# ESP32_WATCH_V1_0.net
KiCad netlist of a schematic drawn in EAGLE
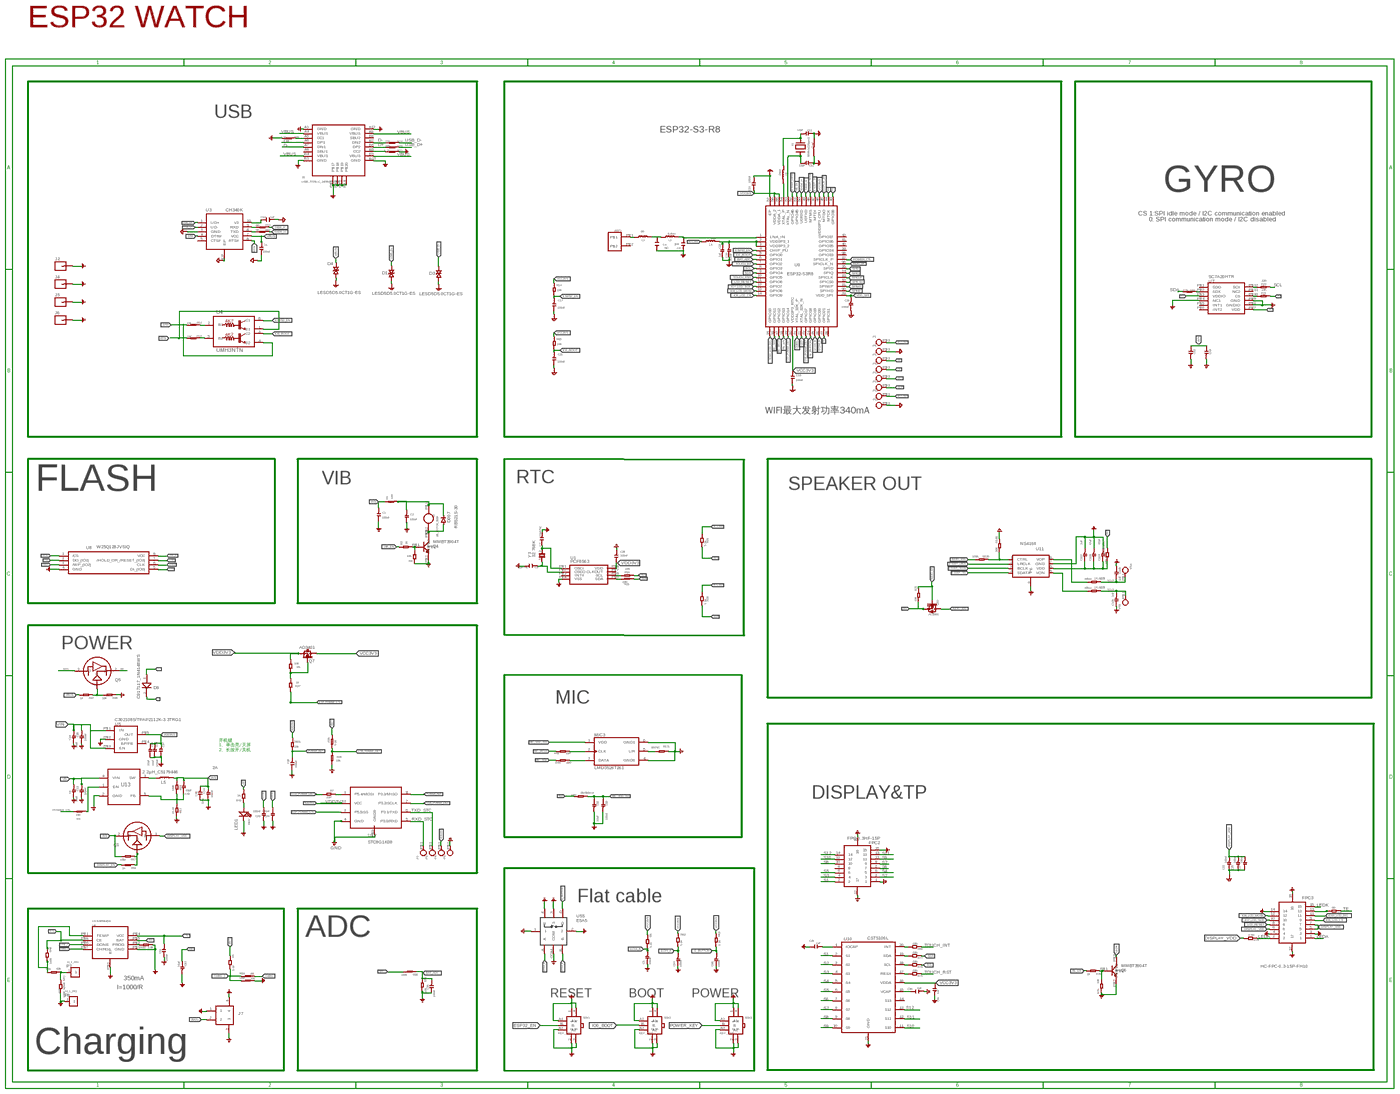
[diagram p0: schematic, sheet 1, overview]
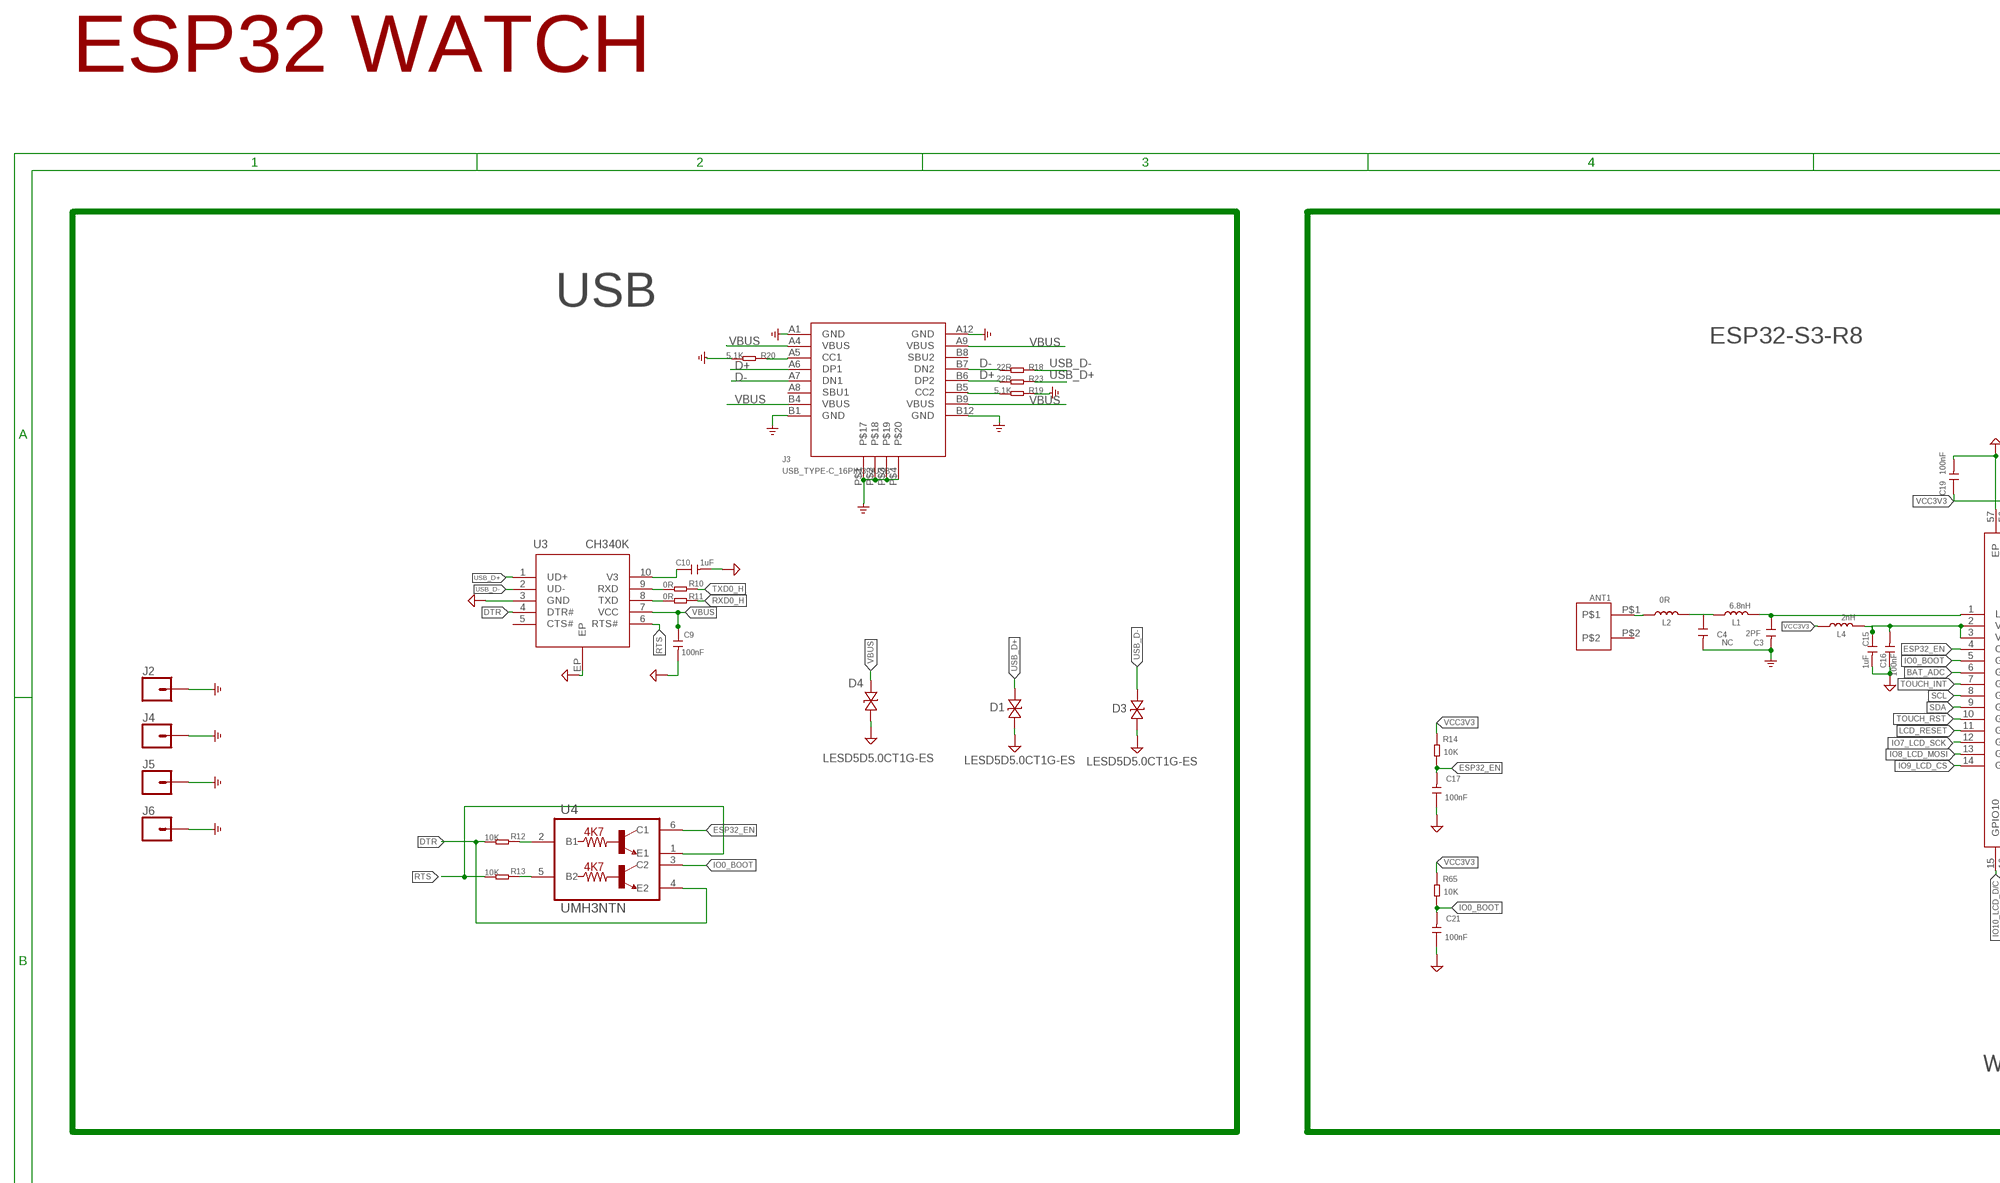
[diagram p1: schematic, sheet 1, part 1 of 4]
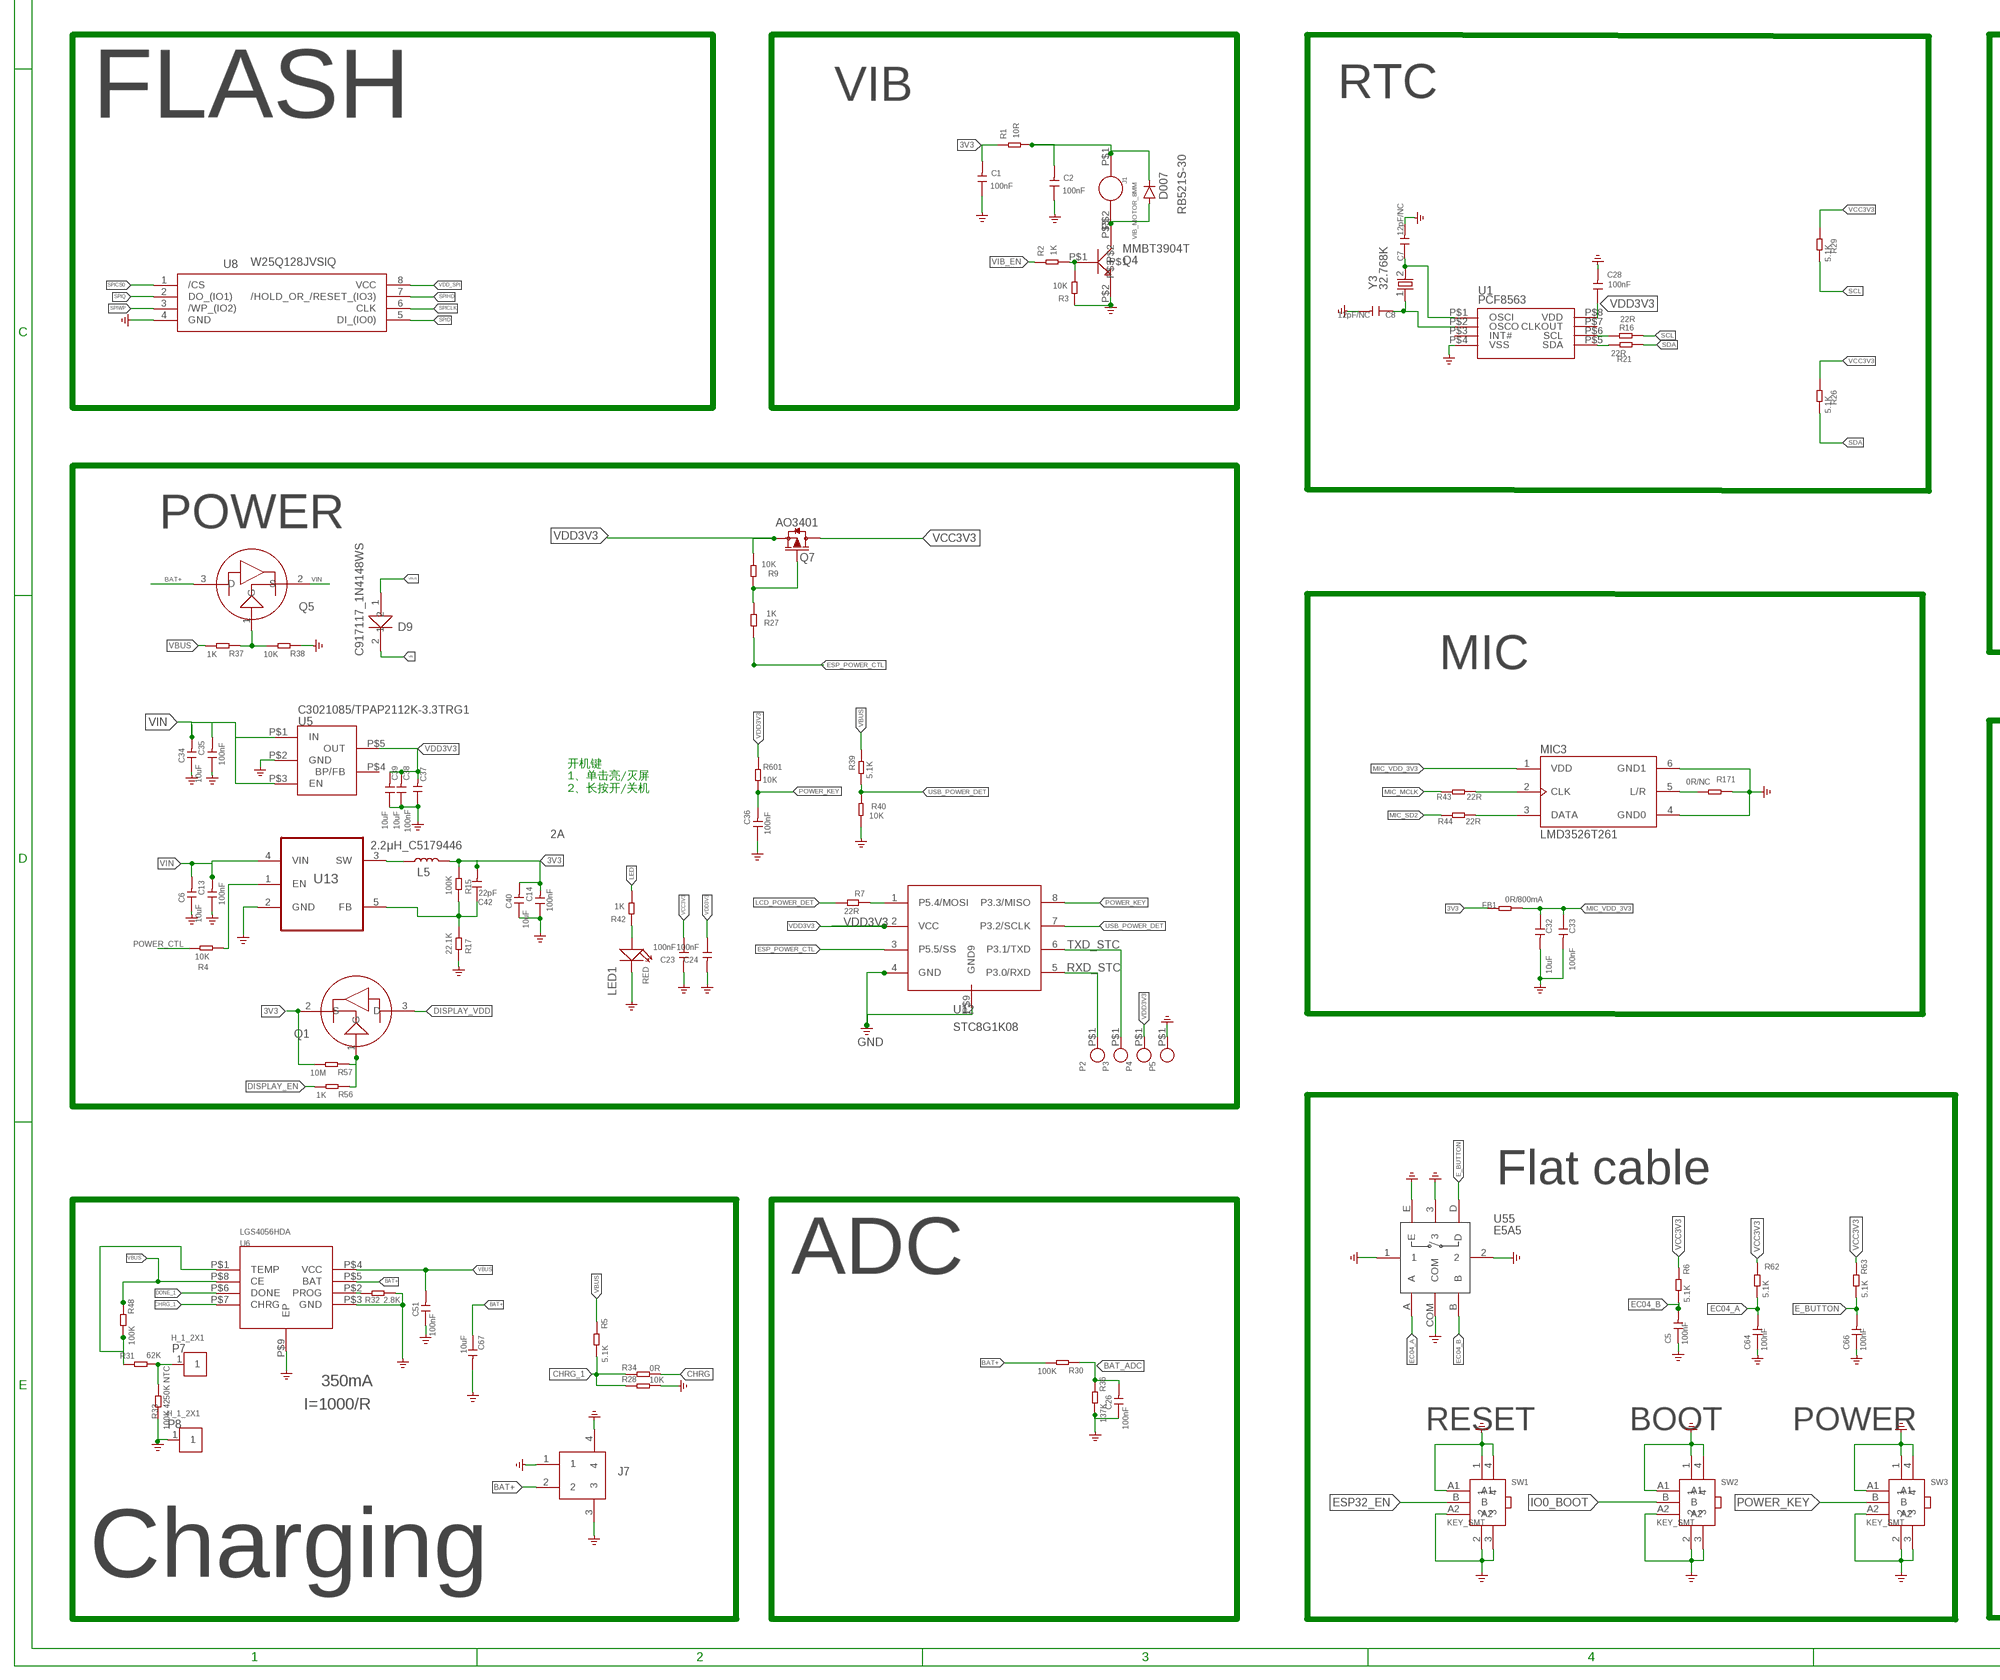
[diagram p2: schematic, sheet 1, part 2 of 4]
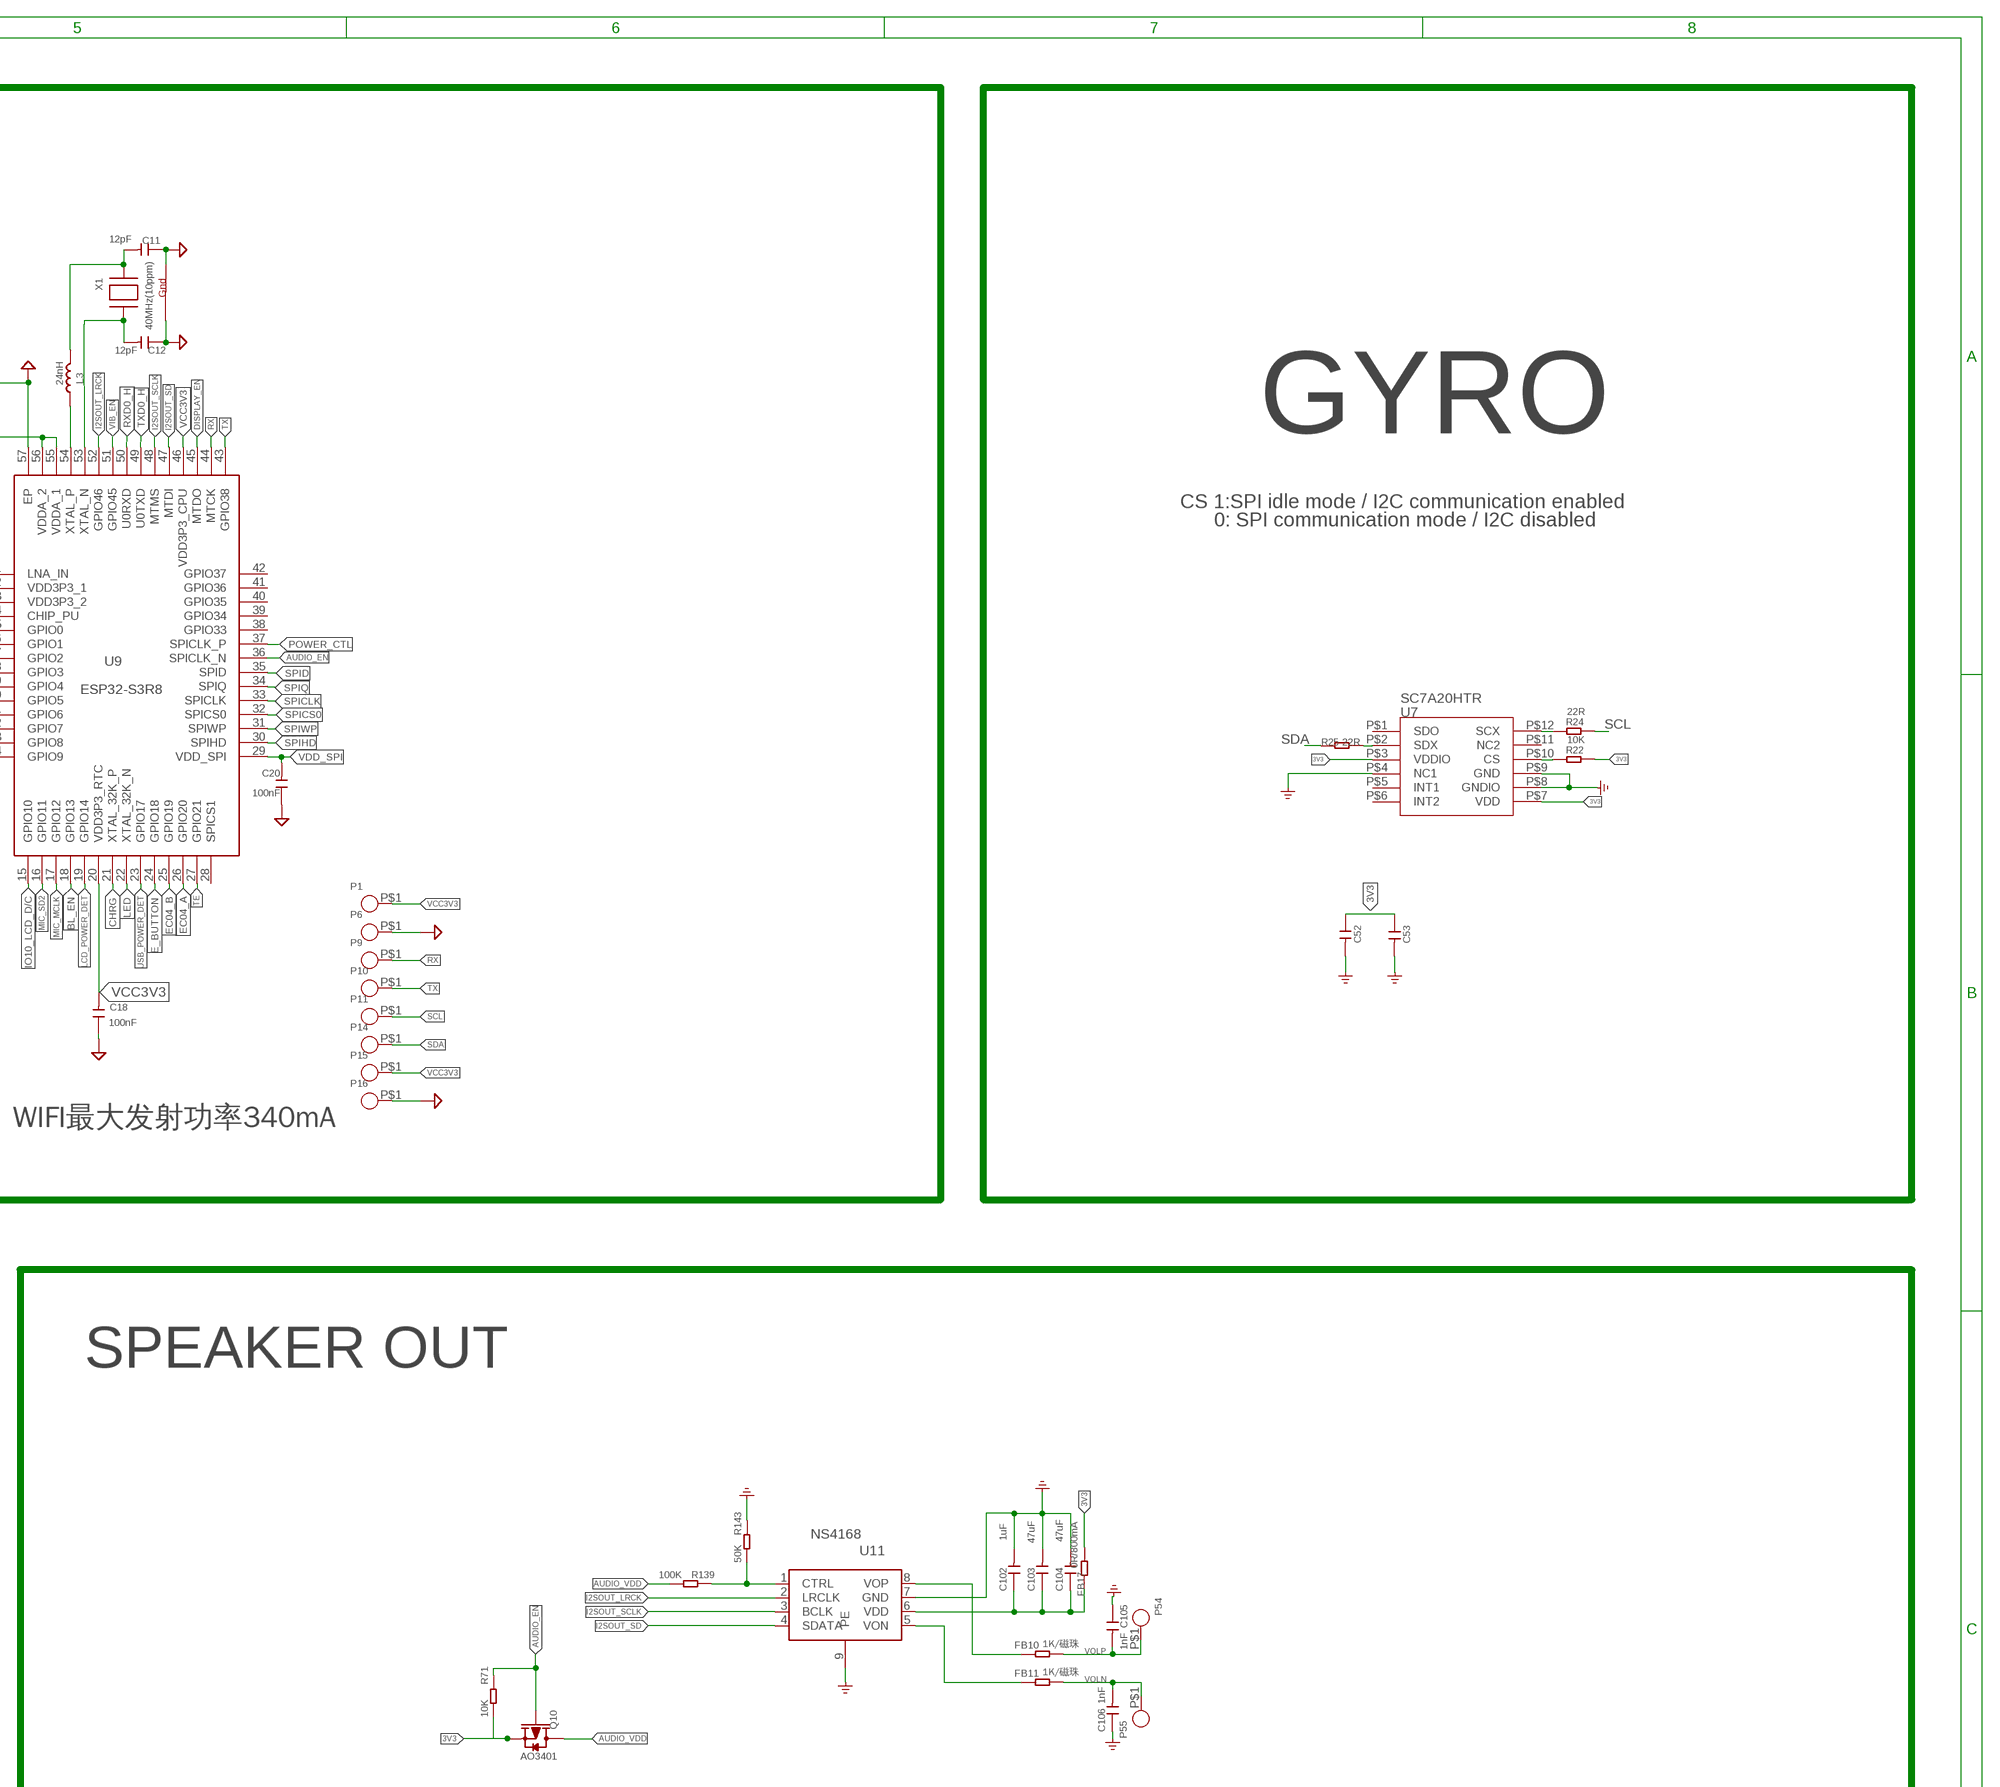
[diagram p3: schematic, sheet 1, part 3 of 4]
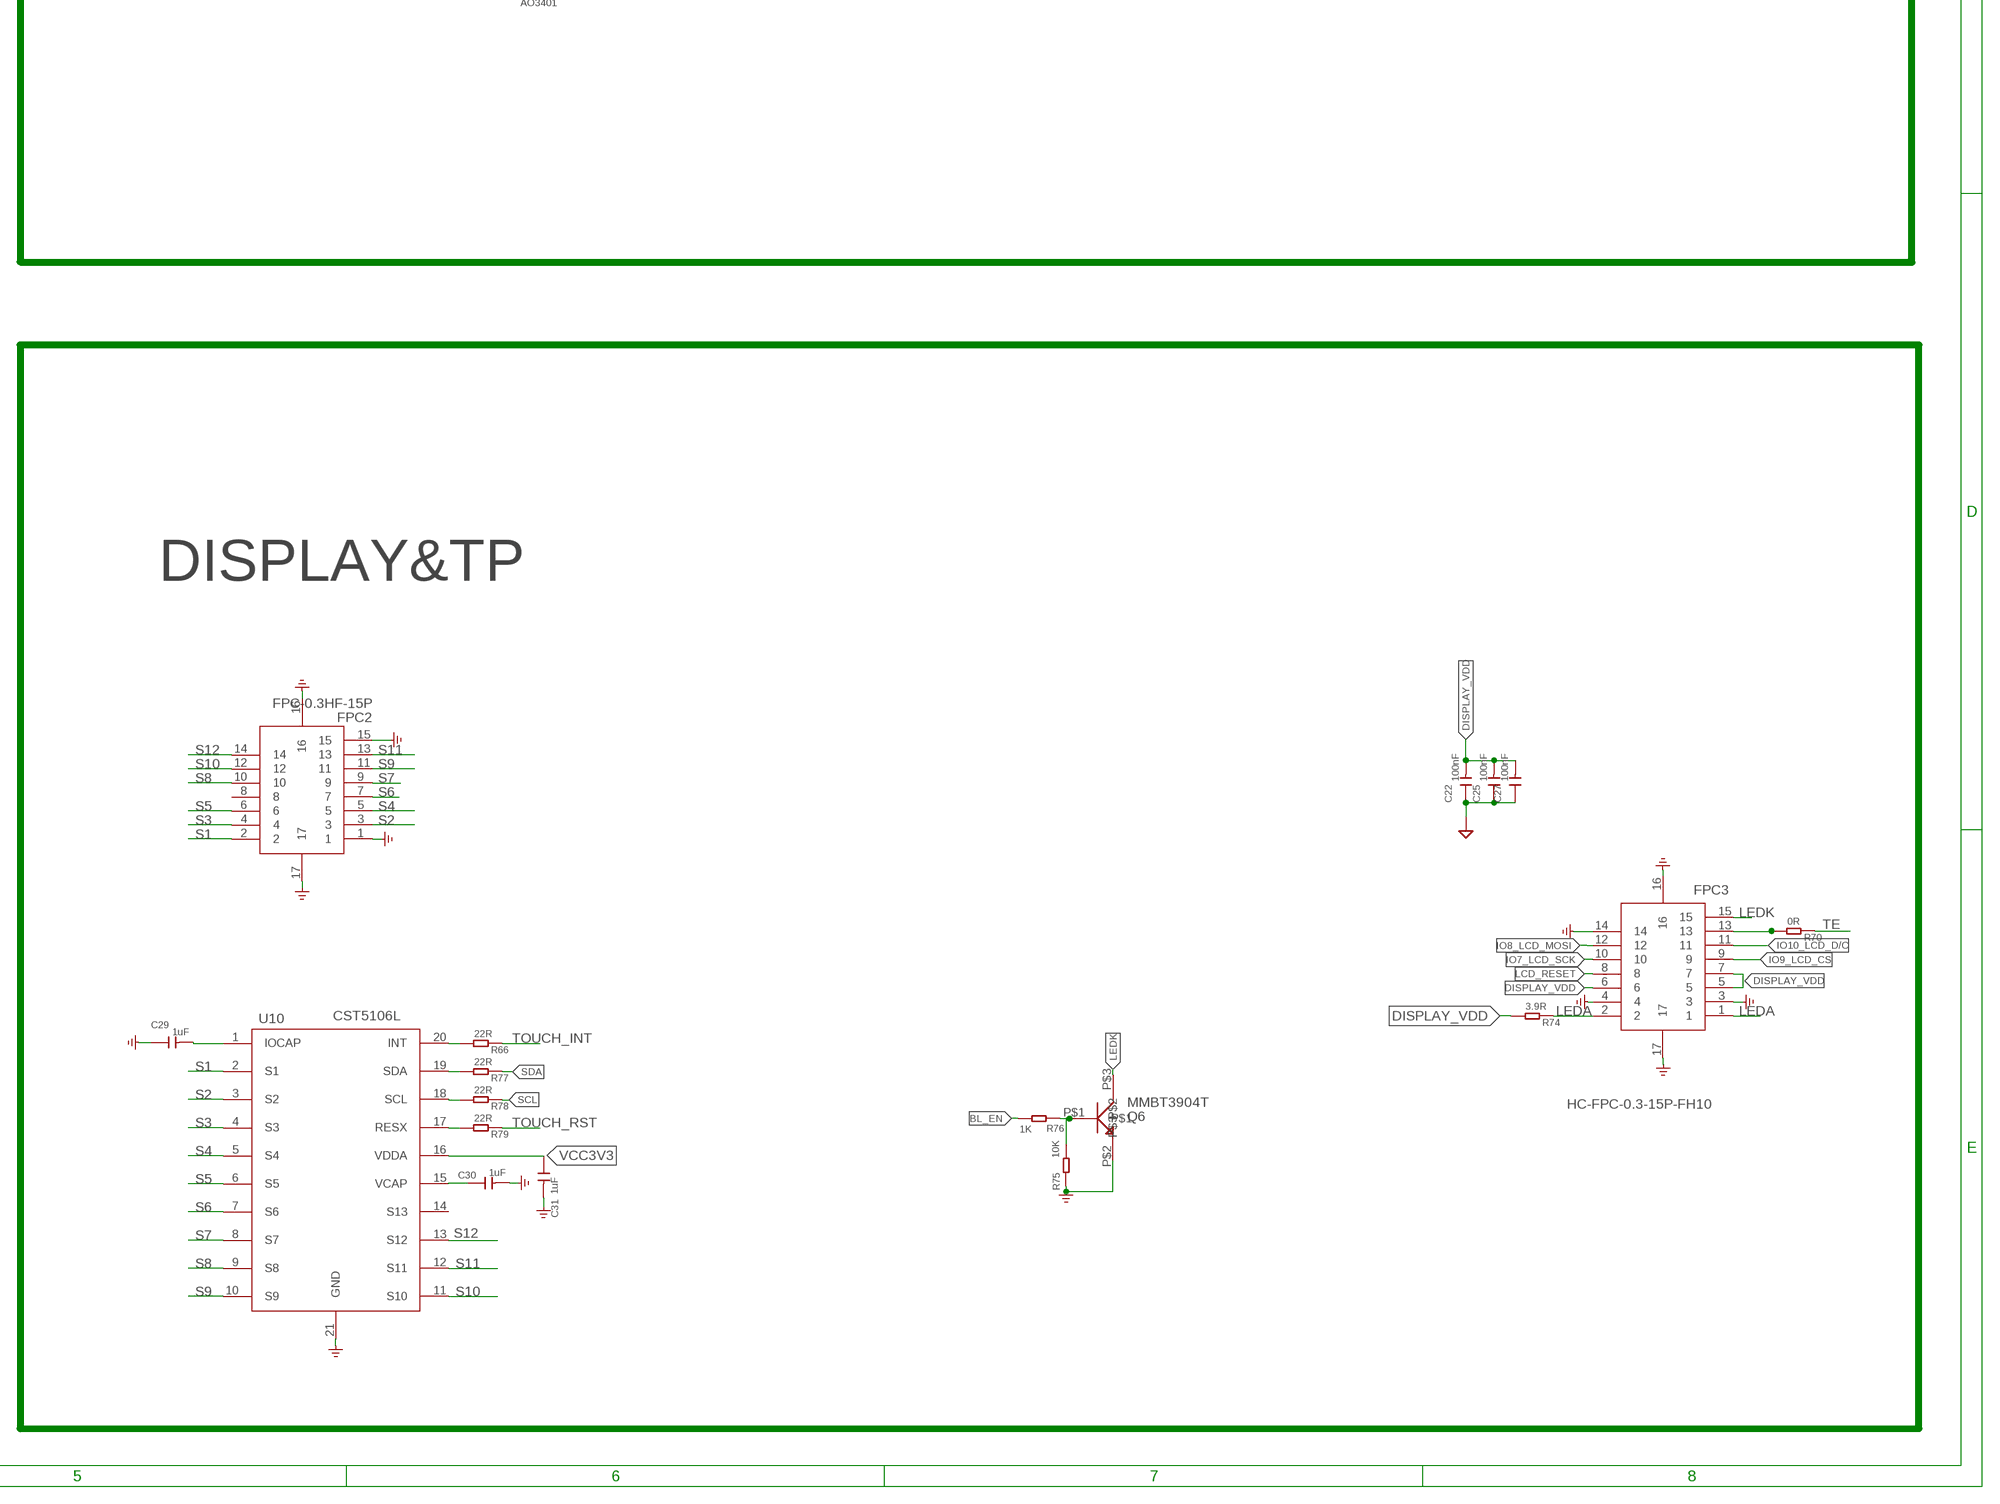
[diagram p4: schematic, sheet 1, part 4 of 4]

(export (version "E")
  (design (tool "Eeschema 10.0.6"))
  (components
    (comp (ref "ANT1")
      (value "OA-D3")
      (footprint "eagle-import:OA-D3")
      (libsource (lib "eagle-import") (part "OA-D3"))
    )
    (comp (ref "C1")
      (value "100nF")
      (footprint "eagle-import:C0402")
      (libsource (lib "eagle-import") (part "CAPC0402-1"))
    )
    (comp (ref "C2")
      (value "100nF")
      (footprint "eagle-import:C0402")
      (libsource (lib "eagle-import") (part "CAPC0402-1"))
    )
    (comp (ref "C3")
      (value "2PF")
      (footprint "eagle-import:C0402")
      (libsource (lib "eagle-import") (part "RC_CAP-0402"))
    )
    (comp (ref "C4")
      (value "NC")
      (footprint "eagle-import:C0402")
      (libsource (lib "eagle-import") (part "RC_CAP-0402"))
    )
    (comp (ref "C5")
      (value "100nF")
      (footprint "eagle-import:C0402")
      (libsource (lib "eagle-import") (part "CAP-0402"))
    )
    (comp (ref "C6")
      (value "10uF")
      (footprint "eagle-import:C0402")
      (libsource (lib "eagle-import") (part "CAP-0402"))
    )
    (comp (ref "C7")
      (value "12pF/NC")
      (footprint "eagle-import:C0402")
      (libsource (lib "eagle-import") (part "CAP-0402"))
    )
    (comp (ref "C8")
      (value "12pF/NC")
      (footprint "eagle-import:C0402")
      (libsource (lib "eagle-import") (part "CAP-0402"))
    )
    (comp (ref "C9")
      (value "100nF")
      (footprint "eagle-import:C0402")
      (libsource (lib "eagle-import") (part "CAPC0402-1"))
    )
    (comp (ref "C10")
      (value "1uF")
      (footprint "eagle-import:C0402")
      (libsource (lib "eagle-import") (part "CAPC0402-1"))
    )
    (comp (ref "C11")
      (value "12pF")
      (footprint "eagle-import:C0402")
      (libsource (lib "eagle-import") (part "CAPC0402-1"))
    )
    (comp (ref "C12")
      (value "12pF")
      (footprint "eagle-import:C0402")
      (libsource (lib "eagle-import") (part "CAPC0402-1"))
    )
    (comp (ref "C13")
      (value "100nF")
      (footprint "eagle-import:C0402")
      (libsource (lib "eagle-import") (part "CAP-0402"))
    )
    (comp (ref "C14")
      (value "100nF")
      (footprint "eagle-import:C0402")
      (libsource (lib "eagle-import") (part "CAP-0402"))
    )
    (comp (ref "C15")
      (value "1uF")
      (footprint "eagle-import:C0402")
      (libsource (lib "eagle-import") (part "CAPC0402-1"))
    )
    (comp (ref "C16")
      (value "100nF")
      (footprint "eagle-import:C0402")
      (libsource (lib "eagle-import") (part "CAPC0402-1"))
    )
    (comp (ref "C17")
      (value "100nF")
      (footprint "eagle-import:C0402")
      (libsource (lib "eagle-import") (part "CAPC0402-1"))
    )
    (comp (ref "C18")
      (value "100nF")
      (footprint "eagle-import:C0402")
      (libsource (lib "eagle-import") (part "CAPC0402-1"))
    )
    (comp (ref "C19")
      (value "100nF")
      (footprint "eagle-import:C0402")
      (libsource (lib "eagle-import") (part "CAPC0402-1"))
    )
    (comp (ref "C20")
      (value "100nF")
      (footprint "eagle-import:C0402")
      (libsource (lib "eagle-import") (part "CAPC0402-1"))
    )
    (comp (ref "C21")
      (value "100nF")
      (footprint "eagle-import:C0402")
      (libsource (lib "eagle-import") (part "CAPC0402-1"))
    )
    (comp (ref "C22")
      (value "100nF")
      (footprint "eagle-import:C0402")
      (libsource (lib "eagle-import") (part "CAPC0402-1"))
    )
    (comp (ref "C23")
      (value "100nF")
      (footprint "eagle-import:C0402")
      (libsource (lib "eagle-import") (part "CAPC0402-1"))
    )
    (comp (ref "C24")
      (value "100nF")
      (footprint "eagle-import:C0402")
      (libsource (lib "eagle-import") (part "CAPC0402-1"))
    )
    (comp (ref "C25")
      (value "100nF")
      (footprint "eagle-import:C0402")
      (libsource (lib "eagle-import") (part "CAPC0402-1"))
    )
    (comp (ref "C26")
      (value "100nF")
      (footprint "eagle-import:C0402")
      (libsource (lib "eagle-import") (part "CAP-0402"))
    )
    (comp (ref "C27")
      (value "100nF")
      (footprint "eagle-import:C0402")
      (libsource (lib "eagle-import") (part "CAPC0402-1"))
    )
    (comp (ref "C28")
      (value "100nF")
      (footprint "eagle-import:C0402")
      (libsource (lib "eagle-import") (part "CAPC0402-1"))
    )
    (comp (ref "C29")
      (value "1uF")
      (footprint "eagle-import:C0402")
      (libsource (lib "eagle-import") (part "CAPC0402-1"))
    )
    (comp (ref "C30")
      (value "1uF")
      (footprint "eagle-import:C0402")
      (libsource (lib "eagle-import") (part "CAPC0402-1"))
    )
    (comp (ref "C31")
      (value "1uF")
      (footprint "eagle-import:C0402")
      (libsource (lib "eagle-import") (part "CAPC0402-1"))
    )
    (comp (ref "C32")
      (value "10uF")
      (footprint "eagle-import:C0402@1")
      (libsource (lib "eagle-import") (part "C0402C0402-1"))
    )
    (comp (ref "C33")
      (value "100nF")
      (footprint "eagle-import:C0402@1")
      (libsource (lib "eagle-import") (part "C0402C0402-1"))
    )
    (comp (ref "C34")
      (value "10uF")
      (footprint "eagle-import:C0402")
      (libsource (lib "eagle-import") (part "CAP-0402"))
    )
    (comp (ref "C35")
      (value "100nF")
      (footprint "eagle-import:C0402")
      (libsource (lib "eagle-import") (part "CAP-0402"))
    )
    (comp (ref "C36")
      (value "100nF")
      (footprint "eagle-import:C0402")
      (libsource (lib "eagle-import") (part "CAP-0402"))
    )
    (comp (ref "C37")
      (value "100nF")
      (footprint "eagle-import:C0402")
      (libsource (lib "eagle-import") (part "CAP-0402"))
    )
    (comp (ref "C38")
      (value "10uF")
      (footprint "eagle-import:C0402")
      (libsource (lib "eagle-import") (part "CAP-0402"))
    )
    (comp (ref "C39")
      (value "10uF")
      (footprint "eagle-import:C0402")
      (libsource (lib "eagle-import") (part "CAP-0402"))
    )
    (comp (ref "C40")
      (value "10uF")
      (footprint "eagle-import:C0402")
      (libsource (lib "eagle-import") (part "CAP-0402"))
    )
    (comp (ref "C42")
      (value "22pF")
      (footprint "eagle-import:C0402")
      (libsource (lib "eagle-import") (part "RC_CAP"))
    )
    (comp (ref "C51")
      (value "100nF")
      (footprint "eagle-import:C0402")
      (libsource (lib "eagle-import") (part "CAP-0402"))
    )
    (comp (ref "C52")
      (value "100nF")
      (footprint "eagle-import:C0402")
      (libsource (lib "eagle-import") (part "CAP-0402"))
    )
    (comp (ref "C53")
      (value "100nF")
      (footprint "eagle-import:C0402")
      (libsource (lib "eagle-import") (part "CAP-0402"))
    )
    (comp (ref "C64")
      (value "100nF")
      (footprint "eagle-import:C0402")
      (libsource (lib "eagle-import") (part "CAP-0402"))
    )
    (comp (ref "C66")
      (value "100nF")
      (footprint "eagle-import:C0402")
      (libsource (lib "eagle-import") (part "CAP-0402"))
    )
    (comp (ref "C67")
      (value "10uF")
      (footprint "eagle-import:DISCRETE-NEW_C0402")
      (libsource (lib "eagle-import") (part "DISCRETE-NEW_CAP-0402"))
    )
    (comp (ref "C102")
      (value "1uF")
      (footprint "eagle-import:C0402@1")
      (libsource (lib "eagle-import") (part "C0402C0402-1"))
    )
    (comp (ref "C103")
      (value "47uF")
      (footprint "eagle-import:C0402")
      (libsource (lib "eagle-import") (part "RC_CAP-0402"))
    )
    (comp (ref "C104")
      (value "47uF")
      (footprint "eagle-import:C0402")
      (libsource (lib "eagle-import") (part "RC_CAP-0402"))
    )
    (comp (ref "C105")
      (value "1nF")
      (footprint "eagle-import:C0402@1")
      (libsource (lib "eagle-import") (part "C0402C0402-1"))
    )
    (comp (ref "C106")
      (value "1nF")
      (footprint "eagle-import:C0402@1")
      (libsource (lib "eagle-import") (part "C0402C0402-1"))
    )
    (comp (ref "D1")
      (value "LESD5D5.0CT1G-ES")
      (footprint "eagle-import:SOD-523_L1.2-W0.8-LS1.6-BI")
      (libsource (lib "eagle-import") (part "LESD5D5.0CT1G-ES"))
    )
    (comp (ref "D3")
      (value "LESD5D5.0CT1G-ES")
      (footprint "eagle-import:SOD-523_L1.2-W0.8-LS1.6-BI")
      (libsource (lib "eagle-import") (part "LESD5D5.0CT1G-ES"))
    )
    (comp (ref "D4")
      (value "LESD5D5.0CT1G-ES")
      (footprint "eagle-import:SOD-523_L1.2-W0.8-LS1.6-BI")
      (libsource (lib "eagle-import") (part "LESD5D5.0CT1G-ES"))
    )
    (comp (ref "D007")
      (value "RB521S-30")
      (footprint "eagle-import:SOD523")
      (libsource (lib "eagle-import") (part "D-SOD523"))
    )
    (comp (ref "D9")
      (value "C917117_1N4148WS")
      (footprint "eagle-import:PICO-2.4_SOD-323")
      (libsource (lib "eagle-import") (part "PICO-2.4_SOD-323"))
    )
    (comp (ref "FB1")
      (value "0R/800mA")
      (footprint "eagle-import:R0402")
      (libsource (lib "eagle-import") (part "R0402-0402"))
    )
    (comp (ref "FB10")
      (value "1K/磁珠")
      (footprint "eagle-import:R0402")
      (libsource (lib "eagle-import") (part "R0402-0402"))
    )
    (comp (ref "FB11")
      (value "1K/磁珠")
      (footprint "eagle-import:R0402")
      (libsource (lib "eagle-import") (part "R0402-0402"))
    )
    (comp (ref "FB17")
      (value "0R/800mA")
      (footprint "eagle-import:R0402")
      (libsource (lib "eagle-import") (part "R0402-0402"))
    )
    (comp (ref "FPC2")
      (value "FPC-0.3HF-15P")
      (footprint "eagle-import:FPC-0.3HF-15P")
      (libsource (lib "eagle-import") (part "FPC-0.3HF-15P"))
    )
    (comp (ref "FPC3")
      (value "HC-FPC-0.3-15P-FH10")
      (footprint "eagle-import:FPC-SMD_HC-FPC-0.3-15P-FH10")
      (libsource (lib "eagle-import") (part "HC-FPC-0.3-15P-FH10"))
    )
    (comp (ref "J1")
      (value "VIB_MOTOR_8MM")
      (footprint "eagle-import:VIB_MOTOR_8MM")
      (libsource (lib "eagle-import") (part "VIB_MOTOR_8MM"))
    )
    (comp (ref "J2")
      (value "CONN_011X01_2.6MM")
      (footprint "eagle-import:1X01_2.5MM")
      (libsource (lib "eagle-import") (part "CONN_011X01_2.6MM"))
    )
    (comp (ref "J3")
      (value "USB_TYPE-C_16PIN3.0USB")
      (footprint "eagle-import:KEVIN_3.0TYPEC-SMD")
      (libsource (lib "eagle-import") (part "USB_TYPE-C_16PIN3.0USB"))
    )
    (comp (ref "J4")
      (value "CONN_011X01_2.6MM")
      (footprint "eagle-import:1X01_2.5MM")
      (libsource (lib "eagle-import") (part "CONN_011X01_2.6MM"))
    )
    (comp (ref "J5")
      (value "CONN_011X01_2.6MM")
      (footprint "eagle-import:1X01_2.5MM")
      (libsource (lib "eagle-import") (part "CONN_011X01_2.6MM"))
    )
    (comp (ref "J6")
      (value "CONN_011X01_2.6MM")
      (footprint "eagle-import:1X01_2.5MM")
      (libsource (lib "eagle-import") (part "CONN_011X01_2.6MM"))
    )
    (comp (ref "J7")
      (value "ZX-SH1.0-2PLT1")
      (footprint "eagle-import:CONN-SMD_2P-P1.00_XUNPU_WAFER-SH1.0-2PWB")
      (libsource (lib "eagle-import") (part "ZX-SH1.0-2PLT1"))
    )
    (comp (ref "L1")
      (value "6.8nH")
      (footprint "eagle-import:L0402")
      (libsource (lib "eagle-import") (part "RC_L0402"))
    )
    (comp (ref "L2")
      (value "0R")
      (footprint "eagle-import:L0402")
      (libsource (lib "eagle-import") (part "RC_L0402"))
    )
    (comp (ref "L3")
      (value "24nH")
      (footprint "eagle-import:L0402")
      (libsource (lib "eagle-import") (part "RC_L0402"))
    )
    (comp (ref "L4")
      (value "2nH")
      (footprint "eagle-import:L0402")
      (libsource (lib "eagle-import") (part "L0402"))
    )
    (comp (ref "L5")
      (value "2.2μH_C5179446")
      (footprint "eagle-import:1008(2520)")
      (libsource (lib "eagle-import") (part "4.7μH_SHIELDED_INDUCTOR"))
    )
    (comp (ref "LED1")
      (value "RED")
      (footprint "eagle-import:LED-0603")
      (libsource (lib "eagle-import") (part "LED'0603'"))
    )
    (comp (ref "MIC3")
      (value "LMD3526T261")
      (footprint "eagle-import:SMD_6P_3.5X2.7MM")
      (libsource (lib "eagle-import") (part "LMD3526T261"))
    )
    (comp (ref "P1")
      (value "TEST_PADPAD-1.5MM")
      (footprint "eagle-import:TEST_PAD-1.5MM")
      (libsource (lib "eagle-import") (part "TEST_PADPAD-1.5MM"))
    )
    (comp (ref "P2")
      (value "TEST_PADPAD-1.5MM")
      (footprint "eagle-import:TEST_PAD-1.5MM")
      (libsource (lib "eagle-import") (part "RC_TEST_PADPAD-1.5MM"))
    )
    (comp (ref "P3")
      (value "TEST_PADPAD-1.5MM")
      (footprint "eagle-import:TEST_PAD-1.5MM")
      (libsource (lib "eagle-import") (part "RC_TEST_PADPAD-1.5MM"))
    )
    (comp (ref "P4")
      (value "TEST_PADPAD-1.5MM")
      (footprint "eagle-import:TEST_PAD-1.5MM")
      (libsource (lib "eagle-import") (part "RC_TEST_PADPAD-1.5MM"))
    )
    (comp (ref "P5")
      (value "TEST_PADPAD-1.5MM")
      (footprint "eagle-import:TEST_PAD-1.5MM")
      (libsource (lib "eagle-import") (part "RC_TEST_PADPAD-1.5MM"))
    )
    (comp (ref "P6")
      (value "TEST_PADPAD-1.5MM")
      (footprint "eagle-import:TEST_PAD-1.5MM")
      (libsource (lib "eagle-import") (part "TEST_PADPAD-1.5MM"))
    )
    (comp (ref "P7")
      (value "H_1_2X1")
      (footprint "eagle-import:H_1_2X1")
      (libsource (lib "eagle-import") (part "H_1_2X1"))
    )
    (comp (ref "P8")
      (value "H_1_2X1")
      (footprint "eagle-import:H_1_2X1")
      (libsource (lib "eagle-import") (part "H_1_2X1"))
    )
    (comp (ref "P9")
      (value "TEST_PADPAD-1.5MM")
      (footprint "eagle-import:TEST_PAD-1.5MM")
      (libsource (lib "eagle-import") (part "TEST_PADPAD-1.5MM"))
    )
    (comp (ref "P10")
      (value "TEST_PADPAD-1.5MM")
      (footprint "eagle-import:TEST_PAD-1.5MM")
      (libsource (lib "eagle-import") (part "TEST_PADPAD-1.5MM"))
    )
    (comp (ref "P11")
      (value "TEST_PADPAD-1.5MM")
      (footprint "eagle-import:TEST_PAD-1.5MM")
      (libsource (lib "eagle-import") (part "TEST_PADPAD-1.5MM"))
    )
    (comp (ref "P14")
      (value "TEST_PADPAD-1.5MM")
      (footprint "eagle-import:TEST_PAD-1.5MM")
      (libsource (lib "eagle-import") (part "TEST_PADPAD-1.5MM"))
    )
    (comp (ref "P15")
      (value "TEST_PADPAD-1.5MM")
      (footprint "eagle-import:TEST_PAD-1.5MM")
      (libsource (lib "eagle-import") (part "TEST_PADPAD-1.5MM"))
    )
    (comp (ref "P16")
      (value "TEST_PADPAD-1.5MM")
      (footprint "eagle-import:TEST_PAD-1.5MM")
      (libsource (lib "eagle-import") (part "TEST_PADPAD-1.5MM"))
    )
    (comp (ref "P54")
      (value "TEST_PADPAD-1.5MM")
      (footprint "eagle-import:TEST_PAD-1.5MM")
      (libsource (lib "eagle-import") (part "TEST_PADPAD-1.5MM"))
    )
    (comp (ref "P55")
      (value "TEST_PADPAD-1.5MM")
      (footprint "eagle-import:TEST_PAD-1.5MM")
      (libsource (lib "eagle-import") (part "TEST_PADPAD-1.5MM"))
    )
    (comp (ref "Q1")
      (value "SI2301")
      (footprint "eagle-import:DFN8_SOT-23")
      (libsource (lib "eagle-import") (part "DFN8_P-MOS-SOT23"))
    )
    (comp (ref "Q4")
      (value "MMBT3904T")
      (footprint "eagle-import:SOT-523")
      (libsource (lib "eagle-import") (part "MMBT3904T-JSM"))
    )
    (comp (ref "Q5")
      (value "SI2301")
      (footprint "eagle-import:DFN8_SOT-23")
      (libsource (lib "eagle-import") (part "DFN8_P-MOS-SOT23"))
    )
    (comp (ref "Q6")
      (value "MMBT3904T")
      (footprint "eagle-import:SOT-523")
      (libsource (lib "eagle-import") (part "MMBT3904T-JSM"))
    )
    (comp (ref "Q7")
      (value "AO3401")
      (footprint "eagle-import:PMOS_SOT23")
      (libsource (lib "eagle-import") (part "MOSFET-PSOT23"))
    )
    (comp (ref "Q10")
      (value "AO3401")
      (footprint "eagle-import:PMOS_SOT23")
      (libsource (lib "eagle-import") (part "CrowPanel_Advance_HMI_MOSFET-PSOT23"))
    )
    (comp (ref "R1")
      (value "10R")
      (footprint "eagle-import:R0402")
      (libsource (lib "eagle-import") (part "RES-0402"))
    )
    (comp (ref "R2")
      (value "1K")
      (footprint "eagle-import:R0402")
      (libsource (lib "eagle-import") (part "RES-0402"))
    )
    (comp (ref "R3")
      (value "10K")
      (footprint "eagle-import:R0402")
      (libsource (lib "eagle-import") (part "RES-0402"))
    )
    (comp (ref "R4")
      (value "10K")
      (footprint "eagle-import:R0402")
      (libsource (lib "eagle-import") (part "RES-0402"))
    )
    (comp (ref "R5")
      (value "5.1K")
      (footprint "eagle-import:R0402")
      (libsource (lib "eagle-import") (part "RES0402"))
    )
    (comp (ref "R6")
      (value "5.1K")
      (footprint "eagle-import:R0402")
      (libsource (lib "eagle-import") (part "RES0402"))
    )
    (comp (ref "R7")
      (value "22R")
      (footprint "eagle-import:R0402")
      (libsource (lib "eagle-import") (part "RESR0402"))
    )
    (comp (ref "R9")
      (value "10K")
      (footprint "eagle-import:R0402")
      (libsource (lib "eagle-import") (part "RESR0402"))
    )
    (comp (ref "R10")
      (value "0R")
      (footprint "eagle-import:R0402")
      (libsource (lib "eagle-import") (part "RES-0402"))
    )
    (comp (ref "R11")
      (value "0R")
      (footprint "eagle-import:R0402")
      (libsource (lib "eagle-import") (part "RES-0402"))
    )
    (comp (ref "R12")
      (value "10K")
      (footprint "eagle-import:R0402")
      (libsource (lib "eagle-import") (part "RES-0402"))
    )
    (comp (ref "R13")
      (value "10K")
      (footprint "eagle-import:R0402")
      (libsource (lib "eagle-import") (part "RES-0402"))
    )
    (comp (ref "R14")
      (value "10K")
      (footprint "eagle-import:R0402")
      (libsource (lib "eagle-import") (part "RES-0402"))
    )
    (comp (ref "R15")
      (value "100K")
      (footprint "eagle-import:0402")
      (libsource (lib "eagle-import") (part "R"))
    )
    (comp (ref "R16")
      (value "22R")
      (footprint "eagle-import:R0402")
      (libsource (lib "eagle-import") (part "RES0402"))
    )
    (comp (ref "R17")
      (value "22.1K")
      (footprint "eagle-import:0402")
      (libsource (lib "eagle-import") (part "R"))
    )
    (comp (ref "R18")
      (value "22R")
      (footprint "eagle-import:0402")
      (libsource (lib "eagle-import") (part "R0402-1"))
    )
    (comp (ref "R19")
      (value "5.1K")
      (footprint "eagle-import:0402")
      (libsource (lib "eagle-import") (part "R0402-1"))
    )
    (comp (ref "R20")
      (value "5.1K")
      (footprint "eagle-import:0402")
      (libsource (lib "eagle-import") (part "R0402-1"))
    )
    (comp (ref "R21")
      (value "22R")
      (footprint "eagle-import:R0402")
      (libsource (lib "eagle-import") (part "RES0402"))
    )
    (comp (ref "R22")
      (value "10K")
      (footprint "eagle-import:R0402")
      (libsource (lib "eagle-import") (part "RES0402"))
    )
    (comp (ref "R23")
      (value "22R")
      (footprint "eagle-import:0402")
      (libsource (lib "eagle-import") (part "R0402-1"))
    )
    (comp (ref "R24")
      (value "22R")
      (footprint "eagle-import:R0402")
      (libsource (lib "eagle-import") (part "RES0402"))
    )
    (comp (ref "R25")
      (value "22R")
      (footprint "eagle-import:R0402")
      (libsource (lib "eagle-import") (part "RES0402"))
    )
    (comp (ref "R26")
      (value "5.1K")
      (footprint "eagle-import:R0402")
      (libsource (lib "eagle-import") (part "RES0402"))
    )
    (comp (ref "R27")
      (value "1K")
      (footprint "eagle-import:R0402")
      (libsource (lib "eagle-import") (part "RESR0402"))
    )
    (comp (ref "R28")
      (value "10K")
      (footprint "eagle-import:R0402")
      (libsource (lib "eagle-import") (part "RES0402"))
    )
    (comp (ref "R29")
      (value "5.1K")
      (footprint "eagle-import:R0402")
      (libsource (lib "eagle-import") (part "RES0402"))
    )
    (comp (ref "R30")
      (value "100K")
      (footprint "eagle-import:R0402")
      (libsource (lib "eagle-import") (part "RES0402"))
    )
    (comp (ref "R31")
      (value "62K")
      (footprint "eagle-import:R0402")
      (libsource (lib "eagle-import") (part "RES0402"))
    )
    (comp (ref "R32")
      (value "2.8K")
      (footprint "eagle-import:R0402")
      (libsource (lib "eagle-import") (part "RES0402"))
    )
    (comp (ref "R33")
      (value "100K 4250K NTC")
      (footprint "eagle-import:R0402")
      (libsource (lib "eagle-import") (part "LoraWAN_Gateway_Mainboard_RES-0402"))
    )
    (comp (ref "R34")
      (value "0R")
      (footprint "eagle-import:R0402")
      (libsource (lib "eagle-import") (part "RES0402"))
    )
    (comp (ref "R36")
      (value "137K")
      (footprint "eagle-import:R0402")
      (libsource (lib "eagle-import") (part "RES0402"))
    )
    (comp (ref "R37")
      (value "1K")
      (footprint "eagle-import:R0402")
      (libsource (lib "eagle-import") (part "RES0402"))
    )
    (comp (ref "R38")
      (value "10K")
      (footprint "eagle-import:R0402")
      (libsource (lib "eagle-import") (part "RES0402"))
    )
    (comp (ref "R39")
      (value "5.1K")
      (footprint "eagle-import:R0402")
      (libsource (lib "eagle-import") (part "RESR0402"))
    )
    (comp (ref "R40")
      (value "10K")
      (footprint "eagle-import:R0402")
      (libsource (lib "eagle-import") (part "RESR0402"))
    )
    (comp (ref "R42")
      (value "1K")
      (footprint "eagle-import:R0402")
      (libsource (lib "eagle-import") (part "RES-0402"))
    )
    (comp (ref "R43")
      (value "22R")
      (footprint "eagle-import:R0402")
      (libsource (lib "eagle-import") (part "R0402-0402"))
    )
    (comp (ref "R44")
      (value "22R")
      (footprint "eagle-import:R0402")
      (libsource (lib "eagle-import") (part "R0402-0402"))
    )
    (comp (ref "R48")
      (value "100K")
      (footprint "eagle-import:R0402")
      (libsource (lib "eagle-import") (part "RES0402"))
    )
    (comp (ref "R56")
      (value "1K")
      (footprint "eagle-import:R0402")
      (libsource (lib "eagle-import") (part "RES0402"))
    )
    (comp (ref "R57")
      (value "10M")
      (footprint "eagle-import:R0402")
      (libsource (lib "eagle-import") (part "RES0402"))
    )
    (comp (ref "R62")
      (value "5.1K")
      (footprint "eagle-import:R0402")
      (libsource (lib "eagle-import") (part "RES0402"))
    )
    (comp (ref "R63")
      (value "5.1K")
      (footprint "eagle-import:R0402")
      (libsource (lib "eagle-import") (part "RES0402"))
    )
    (comp (ref "R65")
      (value "10K")
      (footprint "eagle-import:R0402")
      (libsource (lib "eagle-import") (part "RES-0402"))
    )
    (comp (ref "R66")
      (value "22R")
      (footprint "eagle-import:R0402")
      (libsource (lib "eagle-import") (part "RES-0402"))
    )
    (comp (ref "R70")
      (value "0R")
      (footprint "eagle-import:R0402")
      (libsource (lib "eagle-import") (part "RES-0402"))
    )
    (comp (ref "R71")
      (value "10K")
      (footprint "eagle-import:R0402")
      (libsource (lib "eagle-import") (part "R0402-0402"))
    )
    (comp (ref "R74")
      (value "3.9R")
      (footprint "eagle-import:R0402")
      (libsource (lib "eagle-import") (part "RES-0402"))
    )
    (comp (ref "R75")
      (value "10K")
      (footprint "eagle-import:R0402")
      (libsource (lib "eagle-import") (part "RES0402"))
    )
    (comp (ref "R76")
      (value "1K")
      (footprint "eagle-import:R0402")
      (libsource (lib "eagle-import") (part "RES0402"))
    )
    (comp (ref "R77")
      (value "22R")
      (footprint "eagle-import:R0402")
      (libsource (lib "eagle-import") (part "RES-0402"))
    )
    (comp (ref "R78")
      (value "22R")
      (footprint "eagle-import:R0402")
      (libsource (lib "eagle-import") (part "RES-0402"))
    )
    (comp (ref "R79")
      (value "22R")
      (footprint "eagle-import:R0402")
      (libsource (lib "eagle-import") (part "RES-0402"))
    )
    (comp (ref "R139")
      (value "100K")
      (footprint "eagle-import:R0402")
      (libsource (lib "eagle-import") (part "R0402-0402"))
    )
    (comp (ref "R143")
      (value "50K")
      (footprint "eagle-import:R0402")
      (libsource (lib "eagle-import") (part "R0402-0402"))
    )
    (comp (ref "R171")
      (value "0R/NC")
      (footprint "eagle-import:R0402")
      (libsource (lib "eagle-import") (part "R0402-0402"))
    )
    (comp (ref "R601")
      (value "10K")
      (footprint "eagle-import:R0402")
      (libsource (lib "eagle-import") (part "RESR0402"))
    )
    (comp (ref "SW1")
      (value "KEY_SMT")
      (footprint "eagle-import:SMD_4.1X3.2")
      (libsource (lib "eagle-import") (part "KEY_SMT"))
    )
    (comp (ref "SW2")
      (value "KEY_SMT")
      (footprint "eagle-import:SMD_4.1X3.2")
      (libsource (lib "eagle-import") (part "KEY_SMT"))
    )
    (comp (ref "SW3")
      (value "KEY_SMT")
      (footprint "eagle-import:SMD_4.1X3.2")
      (libsource (lib "eagle-import") (part "KEY_SMT"))
    )
    (comp (ref "U1")
      (value "PCF8563")
      (footprint "eagle-import:MSOP-8")
      (libsource (lib "eagle-import") (part "PCF8563MSOP-8"))
    )
    (comp (ref "U3")
      (value "CH340K")
      (footprint "eagle-import:ESOP-10-EP-150MIL")
      (libsource (lib "eagle-import") (part "CH340K"))
    )
    (comp (ref "U4")
      (value "UMH3NTN")
      (footprint "eagle-import:SOP65P210X100-6N")
      (fields (field (name "MF") "Rohm"))
      (libsource (lib "eagle-import") (part "UMH3NTN"))
    )
    (comp (ref "U5")
      (value "C3021085/TPAP2112K-3.3TRG1")
      (footprint "eagle-import:SOT23-5")
      (libsource (lib "eagle-import") (part "SGM2019"))
    )
    (comp (ref "U6")
      (value "LGS4056HDA")
      (footprint "eagle-import:DFN2X2-8")
      (libsource (lib "eagle-import") (part "LGS4056HDA"))
    )
    (comp (ref "U7")
      (value "SC7A20HTR")
      (footprint "eagle-import:LGA-12(2_2)")
      (libsource (lib "eagle-import") (part "SC7A20HTR"))
    )
    (comp (ref "U8")
      (value "W25Q128JVSIQ")
      (footprint "eagle-import:SOIC127P790X216-8N")
      (fields (field (name "MOUSER_PART_NUMBER") "454-W25Q128JVSIQ"))
      (libsource (lib "eagle-import") (part "W25Q128JVSIQ"))
    )
    (comp (ref "U9")
      (value "ESP32-S3R8")
      (footprint "eagle-import:QFN40P700X700X90-57N")
      (fields (field (name "MOUSER_PART_NUMBER") "356-ESP32-S3R8"))
      (libsource (lib "eagle-import") (part "ESP32-S3R8"))
    )
    (comp (ref "U10")
      (value "CST5106L")
      (footprint "eagle-import:QFN20-3_3")
      (libsource (lib "eagle-import") (part "AXS5106L"))
    )
    (comp (ref "U11")
      (value "NS4168")
      (footprint "eagle-import:NS4168-ESOP-8")
      (libsource (lib "eagle-import") (part "NS4168-ESOP-8"))
    )
    (comp (ref "U12")
      (value "STC8G1K08")
      (footprint "eagle-import:DFN8")
      (libsource (lib "eagle-import") (part "STC8G1K08"))
    )
    (comp (ref "U13")
      (value "MT3406_C22462728")
      (footprint "eagle-import:SOT95P280X145-5N")
      (fields (field (name "MF") "Texas Instruments") (field (name "MP") "TLV62569DBVR"))
      (libsource (lib "eagle-import") (part "TLV62569DBVR"))
    )
    (comp (ref "U55")
      (value "E5A5")
      (footprint "eagle-import:E5A5-2.35S10")
      (libsource (lib "eagle-import") (part "E5A5"))
    )
    (comp (ref "X1")
      (value "40MHz(10ppm)")
      (footprint "eagle-import:ADAFRUIT_NX3225")
      (libsource (lib "eagle-import") (part "ADAFRUIT_XTAL-4-3225"))
    )
    (comp (ref "Y3")
      (value "32.768K")
      (footprint "eagle-import:NORDIC_NRF_XTAL_3215_N")
      (libsource (lib "eagle-import") (part "NORDIC_NRF_XTAL_32KHZ"))
    )
  )
  (nets
    (net (code "1") (name "/D+") (class "Default")
      (node (ref "J3") (pin "A6") (pinfunction "DP1_A6") (pintype "bidirectional"))
      (node (ref "J3") (pin "B6") (pinfunction "DP2_B6") (pintype "bidirectional"))
      (node (ref "R23") (pin "2") (pinfunction "2_2") (pintype "passive"))
    )
    (net (code "2") (name "/D-") (class "Default")
      (node (ref "J3") (pin "A7") (pinfunction "DN1_A7") (pintype "bidirectional"))
      (node (ref "J3") (pin "B7") (pinfunction "DN2_B7") (pintype "bidirectional"))
      (node (ref "R18") (pin "2") (pinfunction "2_2") (pintype "passive"))
    )
    (net (code "3") (name "/LEDA") (class "Default")
      (node (ref "FPC3") (pin "1") (pinfunction "1_1") (pintype "bidirectional"))
      (node (ref "FPC3") (pin "2") (pinfunction "2_2") (pintype "bidirectional"))
      (node (ref "R74") (pin "1") (pinfunction "1_1") (pintype "passive"))
    )
    (net (code "4") (name "/RXD_STC") (class "Default")
      (node (ref "P2") (pin "P$1") (pinfunction "P$1_P$1") (pintype "bidirectional"))
      (node (ref "U12") (pin "5") (pinfunction "P3.0/RXD_5") (pintype "bidirectional"))
    )
    (net (code "5") (name "/S1") (class "Default")
      (node (ref "FPC2") (pin "2") (pinfunction "2_2") (pintype "bidirectional"))
      (node (ref "U10") (pin "2") (pinfunction "S1_2") (pintype "bidirectional"))
    )
    (net (code "6") (name "/S2") (class "Default")
      (node (ref "FPC2") (pin "3") (pinfunction "3_3") (pintype "bidirectional"))
      (node (ref "U10") (pin "3") (pinfunction "S2_3") (pintype "bidirectional"))
    )
    (net (code "7") (name "/S3") (class "Default")
      (node (ref "FPC2") (pin "4") (pinfunction "4_4") (pintype "bidirectional"))
      (node (ref "U10") (pin "4") (pinfunction "S3_4") (pintype "bidirectional"))
    )
    (net (code "8") (name "/S4") (class "Default")
      (node (ref "FPC2") (pin "5") (pinfunction "5_5") (pintype "bidirectional"))
      (node (ref "U10") (pin "5") (pinfunction "S4_5") (pintype "bidirectional"))
    )
    (net (code "9") (name "/S5") (class "Default")
      (node (ref "FPC2") (pin "6") (pinfunction "6_6") (pintype "bidirectional"))
      (node (ref "U10") (pin "6") (pinfunction "S5_6") (pintype "bidirectional"))
    )
    (net (code "10") (name "/S6") (class "Default")
      (node (ref "FPC2") (pin "7") (pinfunction "7_7") (pintype "bidirectional"))
      (node (ref "U10") (pin "7") (pinfunction "S6_7") (pintype "bidirectional"))
    )
    (net (code "11") (name "/S7") (class "Default")
      (node (ref "FPC2") (pin "9") (pinfunction "9_9") (pintype "bidirectional"))
      (node (ref "U10") (pin "8") (pinfunction "S7_8") (pintype "bidirectional"))
    )
    (net (code "12") (name "/S8") (class "Default")
      (node (ref "FPC2") (pin "10") (pinfunction "10_10") (pintype "bidirectional"))
      (node (ref "U10") (pin "9") (pinfunction "S8_9") (pintype "bidirectional"))
    )
    (net (code "13") (name "/S9") (class "Default")
      (node (ref "FPC2") (pin "11") (pinfunction "11_11") (pintype "bidirectional"))
      (node (ref "U10") (pin "10") (pinfunction "S9_10") (pintype "bidirectional"))
    )
    (net (code "14") (name "/S10") (class "Default")
      (node (ref "FPC2") (pin "12") (pinfunction "12_12") (pintype "bidirectional"))
      (node (ref "U10") (pin "11") (pinfunction "S10_11") (pintype "bidirectional"))
    )
    (net (code "15") (name "/S11") (class "Default")
      (node (ref "FPC2") (pin "13") (pinfunction "13_13") (pintype "bidirectional"))
      (node (ref "U10") (pin "12") (pinfunction "S11_12") (pintype "bidirectional"))
    )
    (net (code "16") (name "/S12") (class "Default")
      (node (ref "FPC2") (pin "14") (pinfunction "14_14") (pintype "bidirectional"))
      (node (ref "U10") (pin "13") (pinfunction "S12_13") (pintype "bidirectional"))
    )
    (net (code "17") (name "/TXD_STC") (class "Default")
      (node (ref "P3") (pin "P$1") (pinfunction "P$1_P$1") (pintype "bidirectional"))
      (node (ref "U12") (pin "6") (pinfunction "P3.1/TXD_6") (pintype "bidirectional"))
    )
    (net (code "18") (name "/VOLN") (class "Default")
      (node (ref "C106") (pin "2") (pinfunction "2_2") (pintype "passive"))
      (node (ref "FB11") (pin "2") (pinfunction "2_2") (pintype "passive"))
      (node (ref "P55") (pin "P$1") (pinfunction "P$1_P$1") (pintype "bidirectional"))
    )
    (net (code "19") (name "/VOLP") (class "Default")
      (node (ref "C105") (pin "2") (pinfunction "2_2") (pintype "passive"))
      (node (ref "FB10") (pin "2") (pinfunction "2_2") (pintype "passive"))
      (node (ref "P54") (pin "P$1") (pinfunction "P$1_P$1") (pintype "bidirectional"))
    )
    (net (code "20") (name "3V3") (class "Default")
      (node (ref "C1") (pin "2") (pinfunction "2_2") (pintype "passive"))
      (node (ref "C14") (pin "2") (pinfunction "2_2") (pintype "passive"))
      (node (ref "C40") (pin "2") (pinfunction "2_2") (pintype "passive"))
      (node (ref "C42") (pin "2") (pinfunction "2_2") (pintype "passive"))
      (node (ref "C52") (pin "1") (pinfunction "1_1") (pintype "passive"))
      (node (ref "C53") (pin "1") (pinfunction "1_1") (pintype "passive"))
      (node (ref "FB1") (pin "1") (pinfunction "1_1") (pintype "passive"))
      (node (ref "FB17") (pin "2") (pinfunction "2_2") (pintype "passive"))
      (node (ref "L5") (pin "2") (pinfunction "2_2") (pintype "passive"))
      (node (ref "Q1") (pin "2") (pinfunction "S_2") (pintype "bidirectional"))
      (node (ref "Q10") (pin "2") (pinfunction "S_2") (pintype "passive"))
      (node (ref "R1") (pin "1") (pinfunction "1_1") (pintype "passive"))
      (node (ref "R15") (pin "1") (pinfunction "1_1") (pintype "passive"))
      (node (ref "R22") (pin "1") (pinfunction "1_1") (pintype "passive"))
      (node (ref "R57") (pin "2") (pinfunction "2_2") (pintype "passive"))
      (node (ref "R71") (pin "2") (pinfunction "2_2") (pintype "passive"))
      (node (ref "U7") (pin "P$3") (pinfunction "VDDIO_P$3") (pintype "bidirectional"))
      (node (ref "U7") (pin "P$7") (pinfunction "VDD_P$7") (pintype "bidirectional"))
    )
    (net (code "21") (name "AUDIO_EN") (class "Default")
      (node (ref "Q10") (pin "1") (pinfunction "G_1") (pintype "passive"))
      (node (ref "R71") (pin "1") (pinfunction "1_1") (pintype "passive"))
      (node (ref "U9") (pin "36") (pinfunction "SPICLK_N_36") (pintype "bidirectional"))
    )
    (net (code "22") (name "AUDIO_VDD") (class "Default")
      (node (ref "Q10") (pin "3") (pinfunction "D_3") (pintype "passive"))
      (node (ref "R139") (pin "2") (pinfunction "2_2") (pintype "passive"))
    )
    (net (code "23") (name "A_XBJ_POWER_OR_GND__GND_POWER") (class "Default")
      (node (ref "C1") (pin "1") (pinfunction "1_1") (pintype "passive"))
      (node (ref "C10") (pin "2") (pinfunction "2_2") (pintype "passive"))
      (node (ref "C102") (pin "2") (pinfunction "2_2") (pintype "passive"))
      (node (ref "C103") (pin "2") (pinfunction "2_2") (pintype "passive"))
      (node (ref "C104") (pin "2") (pinfunction "2_2") (pintype "passive"))
      (node (ref "C105") (pin "1") (pinfunction "1_1") (pintype "passive"))
      (node (ref "C106") (pin "1") (pinfunction "1_1") (pintype "passive"))
      (node (ref "C11") (pin "1") (pinfunction "1_1") (pintype "passive"))
      (node (ref "C12") (pin "1") (pinfunction "1_1") (pintype "passive"))
      (node (ref "C13") (pin "1") (pinfunction "1_1") (pintype "passive"))
      (node (ref "C14") (pin "1") (pinfunction "1_1") (pintype "passive"))
      (node (ref "C15") (pin "2") (pinfunction "2_2") (pintype "passive"))
      (node (ref "C16") (pin "1") (pinfunction "1_1") (pintype "passive"))
      (node (ref "C17") (pin "1") (pinfunction "1_1") (pintype "passive"))
      (node (ref "C18") (pin "1") (pinfunction "1_1") (pintype "passive"))
      (node (ref "C19") (pin "2") (pinfunction "2_2") (pintype "passive"))
      (node (ref "C2") (pin "1") (pinfunction "1_1") (pintype "passive"))
      (node (ref "C20") (pin "1") (pinfunction "1_1") (pintype "passive"))
      (node (ref "C21") (pin "1") (pinfunction "1_1") (pintype "passive"))
      (node (ref "C22") (pin "1") (pinfunction "1_1") (pintype "passive"))
      (node (ref "C23") (pin "2") (pinfunction "2_2") (pintype "passive"))
      (node (ref "C24") (pin "2") (pinfunction "2_2") (pintype "passive"))
      (node (ref "C25") (pin "1") (pinfunction "1_1") (pintype "passive"))
      (node (ref "C26") (pin "1") (pinfunction "1_1") (pintype "passive"))
      (node (ref "C27") (pin "1") (pinfunction "1_1") (pintype "passive"))
      (node (ref "C28") (pin "2") (pinfunction "2_2") (pintype "passive"))
      (node (ref "C29") (pin "1") (pinfunction "1_1") (pintype "passive"))
      (node (ref "C3") (pin "2") (pinfunction "2_2") (pintype "passive"))
      (node (ref "C30") (pin "2") (pinfunction "2_2") (pintype "passive"))
      (node (ref "C31") (pin "2") (pinfunction "2_2") (pintype "passive"))
      (node (ref "C32") (pin "2") (pinfunction "2_2") (pintype "passive"))
      (node (ref "C33") (pin "2") (pinfunction "2_2") (pintype "passive"))
      (node (ref "C34") (pin "1") (pinfunction "1_1") (pintype "passive"))
      (node (ref "C35") (pin "1") (pinfunction "1_1") (pintype "passive"))
      (node (ref "C36") (pin "1") (pinfunction "1_1") (pintype "passive"))
      (node (ref "C37") (pin "1") (pinfunction "1_1") (pintype "passive"))
      (node (ref "C38") (pin "1") (pinfunction "1_1") (pintype "passive"))
      (node (ref "C39") (pin "1") (pinfunction "1_1") (pintype "passive"))
      (node (ref "C4") (pin "2") (pinfunction "2_2") (pintype "passive"))
      (node (ref "C40") (pin "1") (pinfunction "1_1") (pintype "passive"))
      (node (ref "C5") (pin "1") (pinfunction "1_1") (pintype "passive"))
      (node (ref "C51") (pin "1") (pinfunction "1_1") (pintype "passive"))
      (node (ref "C52") (pin "2") (pinfunction "2_2") (pintype "passive"))
      (node (ref "C53") (pin "2") (pinfunction "2_2") (pintype "passive"))
      (node (ref "C6") (pin "1") (pinfunction "1_1") (pintype "passive"))
      (node (ref "C64") (pin "1") (pinfunction "1_1") (pintype "passive"))
      (node (ref "C66") (pin "1") (pinfunction "1_1") (pintype "passive"))
      (node (ref "C67") (pin "2") (pinfunction "2_2") (pintype "passive"))
      (node (ref "C7") (pin "2") (pinfunction "2_2") (pintype "passive"))
      (node (ref "C8") (pin "2") (pinfunction "2_2") (pintype "passive"))
      (node (ref "C9") (pin "2") (pinfunction "2_2") (pintype "passive"))
      (node (ref "D1") (pin "1") (pinfunction "1_1") (pintype "bidirectional"))
      (node (ref "D3") (pin "1") (pinfunction "1_1") (pintype "bidirectional"))
      (node (ref "D4") (pin "1") (pinfunction "1_1") (pintype "bidirectional"))
      (node (ref "FPC2") (pin "1") (pinfunction "1_1") (pintype "bidirectional"))
      (node (ref "FPC2") (pin "15") (pinfunction "15_15") (pintype "bidirectional"))
      (node (ref "FPC2") (pin "16") (pinfunction "16_16") (pintype "bidirectional"))
      (node (ref "FPC2") (pin "17") (pinfunction "17_17") (pintype "bidirectional"))
      (node (ref "FPC3") (pin "14") (pinfunction "14_14") (pintype "bidirectional"))
      (node (ref "FPC3") (pin "16") (pinfunction "16_16") (pintype "bidirectional"))
      (node (ref "FPC3") (pin "17") (pinfunction "17_17") (pintype "bidirectional"))
      (node (ref "FPC3") (pin "3") (pinfunction "3_3") (pintype "bidirectional"))
      (node (ref "FPC3") (pin "4") (pinfunction "4_4") (pintype "bidirectional"))
      (node (ref "J2") (pin "1") (pinfunction "1_1") (pintype "passive"))
      (node (ref "J3") (pin "A1") (pinfunction "GND_A1") (pintype "bidirectional"))
      (node (ref "J3") (pin "A12") (pinfunction "GND_A12") (pintype "bidirectional"))
      (node (ref "J3") (pin "B1") (pinfunction "GND_B1") (pintype "bidirectional"))
      (node (ref "J3") (pin "B12") (pinfunction "GND_B12") (pintype "bidirectional"))
      (node (ref "J3") (pin "P$1") (pinfunction "P$17_P$1") (pintype "bidirectional"))
      (node (ref "J3") (pin "P$2") (pinfunction "P$18_P$2") (pintype "bidirectional"))
      (node (ref "J3") (pin "P$3") (pinfunction "P$19_P$3") (pintype "bidirectional"))
      (node (ref "J3") (pin "P$4") (pinfunction "P$20_P$4") (pintype "bidirectional"))
      (node (ref "J4") (pin "1") (pinfunction "1_1") (pintype "passive"))
      (node (ref "J5") (pin "1") (pinfunction "1_1") (pintype "passive"))
      (node (ref "J6") (pin "1") (pinfunction "1_1") (pintype "passive"))
      (node (ref "J7") (pin "1") (pinfunction "1_1") (pintype "bidirectional"))
      (node (ref "J7") (pin "3") (pinfunction "3_3") (pintype "bidirectional"))
      (node (ref "J7") (pin "4") (pinfunction "4_4") (pintype "bidirectional"))
      (node (ref "LED1") (pin "-") (pinfunction "-_-") (pintype "passive"))
      (node (ref "MIC3") (pin "4") (pinfunction "GND0_4") (pintype "power_in"))
      (node (ref "MIC3") (pin "6") (pinfunction "GND1_6") (pintype "power_in"))
      (node (ref "P16") (pin "P$1") (pinfunction "P$1_P$1") (pintype "bidirectional"))
      (node (ref "P5") (pin "P$1") (pinfunction "P$1_P$1") (pintype "bidirectional"))
      (node (ref "P6") (pin "P$1") (pinfunction "P$1_P$1") (pintype "bidirectional"))
      (node (ref "P8") (pin "1") (pinfunction "1_1") (pintype "bidirectional"))
      (node (ref "Q4") (pin "P$2") (pinfunction "P$2_P$2") (pintype "bidirectional"))
      (node (ref "Q6") (pin "P$2") (pinfunction "P$2_P$2") (pintype "bidirectional"))
      (node (ref "R143") (pin "1") (pinfunction "1_1") (pintype "passive"))
      (node (ref "R17") (pin "2") (pinfunction "2_2") (pintype "passive"))
      (node (ref "R171") (pin "2") (pinfunction "2_2") (pintype "passive"))
      (node (ref "R19") (pin "1") (pinfunction "1_1") (pintype "passive"))
      (node (ref "R20") (pin "2") (pinfunction "2_2") (pintype "passive"))
      (node (ref "R28") (pin "2") (pinfunction "2_2") (pintype "passive"))
      (node (ref "R3") (pin "1") (pinfunction "1_1") (pintype "passive"))
      (node (ref "R32") (pin "2") (pinfunction "2_2") (pintype "passive"))
      (node (ref "R33") (pin "1") (pinfunction "1_1") (pintype "passive"))
      (node (ref "R36") (pin "2") (pinfunction "2_2") (pintype "passive"))
      (node (ref "R38") (pin "1") (pinfunction "1_1") (pintype "passive"))
      (node (ref "R40") (pin "1") (pinfunction "1_1") (pintype "passive"))
      (node (ref "R75") (pin "1") (pinfunction "1_1") (pintype "passive"))
      (node (ref "SW1") (pin "1") (pinfunction "1_1") (pintype "bidirectional"))
      (node (ref "SW1") (pin "2") (pinfunction "2_2") (pintype "bidirectional"))
      (node (ref "SW1") (pin "3") (pinfunction "3_3") (pintype "bidirectional"))
      (node (ref "SW1") (pin "4") (pinfunction "4_4") (pintype "bidirectional"))
      (node (ref "SW1") (pin "A1") (pinfunction "A1_A1") (pintype "bidirectional"))
      (node (ref "SW1") (pin "A2") (pinfunction "A2_A2") (pintype "bidirectional"))
      (node (ref "SW2") (pin "1") (pinfunction "1_1") (pintype "bidirectional"))
      (node (ref "SW2") (pin "2") (pinfunction "2_2") (pintype "bidirectional"))
      (node (ref "SW2") (pin "3") (pinfunction "3_3") (pintype "bidirectional"))
      (node (ref "SW2") (pin "4") (pinfunction "4_4") (pintype "bidirectional"))
      (node (ref "SW2") (pin "A1") (pinfunction "A1_A1") (pintype "bidirectional"))
      (node (ref "SW2") (pin "A2") (pinfunction "A2_A2") (pintype "bidirectional"))
      (node (ref "SW3") (pin "1") (pinfunction "1_1") (pintype "bidirectional"))
      (node (ref "SW3") (pin "2") (pinfunction "2_2") (pintype "bidirectional"))
      (node (ref "SW3") (pin "3") (pinfunction "3_3") (pintype "bidirectional"))
      (node (ref "SW3") (pin "4") (pinfunction "4_4") (pintype "bidirectional"))
      (node (ref "SW3") (pin "A1") (pinfunction "A1_A1") (pintype "bidirectional"))
      (node (ref "SW3") (pin "A2") (pinfunction "A2_A2") (pintype "bidirectional"))
      (node (ref "U1") (pin "P$4") (pinfunction "VSS_P$4") (pintype "bidirectional"))
      (node (ref "U10") (pin "21") (pinfunction "GND_21") (pintype "bidirectional"))
      (node (ref "U11") (pin "7") (pinfunction "GND_7") (pintype "bidirectional"))
      (node (ref "U11") (pin "9") (pinfunction "PE_9") (pintype "bidirectional"))
      (node (ref "U12") (pin "4") (pinfunction "GND_4") (pintype "bidirectional"))
      (node (ref "U12") (pin "P$9") (pinfunction "GND9_P$9") (pintype "bidirectional"))
      (node (ref "U13") (pin "2") (pinfunction "GND_2") (pintype "power_in"))
      (node (ref "U3") (pin "3") (pinfunction "GND_3") (pintype "bidirectional"))
      (node (ref "U3") (pin "EP") (pinfunction "EP_EP") (pintype "bidirectional"))
      (node (ref "U5") (pin "P$2") (pinfunction "GND_P$2") (pintype "bidirectional"))
      (node (ref "U55") (pin "1") (pinfunction "1_1") (pintype "bidirectional"))
      (node (ref "U55") (pin "2") (pinfunction "2_2") (pintype "bidirectional"))
      (node (ref "U55") (pin "3") (pinfunction "3_3") (pintype "bidirectional"))
      (node (ref "U55") (pin "COM") (pinfunction "COM_COM") (pintype "bidirectional"))
      (node (ref "U55") (pin "E") (pinfunction "E_E") (pintype "bidirectional"))
      (node (ref "U6") (pin "P$3") (pinfunction "GND_P$3") (pintype "bidirectional"))
      (node (ref "U6") (pin "P$9") (pinfunction "EP_P$9") (pintype "bidirectional"))
      (node (ref "U7") (pin "P$4") (pinfunction "NC1_P$4") (pintype "bidirectional"))
      (node (ref "U7") (pin "P$8") (pinfunction "GNDIO_P$8") (pintype "bidirectional"))
      (node (ref "U7") (pin "P$9") (pinfunction "GND_P$9") (pintype "bidirectional"))
      (node (ref "U8") (pin "4") (pinfunction "GND_4") (pintype "bidirectional"))
      (node (ref "U9") (pin "57") (pinfunction "EP_57") (pintype "bidirectional"))
      (node (ref "X1") (pin "2") (pinfunction "G2_2") (pintype "power_in"))
      (node (ref "X1") (pin "4") (pinfunction "G1_4") (pintype "power_in"))
    )
    (net (code "24") (name "BAT+") (class "Default")
      (node (ref "C67") (pin "1") (pinfunction "1_1") (pintype "passive"))
      (node (ref "J7") (pin "2") (pinfunction "2_2") (pintype "bidirectional"))
      (node (ref "Q5") (pin "3") (pinfunction "D_3") (pintype "bidirectional"))
      (node (ref "R30") (pin "2") (pinfunction "2_2") (pintype "passive"))
      (node (ref "U6") (pin "P$5") (pinfunction "BAT_P$5") (pintype "bidirectional"))
    )
    (net (code "25") (name "BAT_ADC") (class "Default")
      (node (ref "C26") (pin "2") (pinfunction "2_2") (pintype "passive"))
      (node (ref "R30") (pin "1") (pinfunction "1_1") (pintype "passive"))
      (node (ref "R36") (pin "1") (pinfunction "1_1") (pintype "passive"))
      (node (ref "U9") (pin "6") (pinfunction "GPIO1_6") (pintype "bidirectional"))
    )
    (net (code "26") (name "BL_EN") (class "Default")
      (node (ref "R76") (pin "2") (pinfunction "2_2") (pintype "passive"))
      (node (ref "U9") (pin "18") (pinfunction "GPIO13_18") (pintype "bidirectional"))
    )
    (net (code "27") (name "CHRG") (class "Default")
      (node (ref "R34") (pin "2") (pinfunction "2_2") (pintype "passive"))
      (node (ref "U9") (pin "21") (pinfunction "XTAL_32K_P_21") (pintype "bidirectional"))
    )
    (net (code "28") (name "CHRG_1") (class "Default")
      (node (ref "R28") (pin "1") (pinfunction "1_1") (pintype "passive"))
      (node (ref "R34") (pin "1") (pinfunction "1_1") (pintype "passive"))
      (node (ref "R5") (pin "2") (pinfunction "2_2") (pintype "passive"))
      (node (ref "U6") (pin "P$7") (pinfunction "CHRG_P$7") (pintype "bidirectional"))
    )
    (net (code "29") (name "DISPLAY_EN") (class "Default")
      (node (ref "R56") (pin "2") (pinfunction "2_2") (pintype "passive"))
      (node (ref "U9") (pin "45") (pinfunction "MTDO_45") (pintype "bidirectional"))
    )
    (net (code "30") (name "DISPLAY_VDD") (class "Default")
      (node (ref "C22") (pin "2") (pinfunction "2_2") (pintype "passive"))
      (node (ref "C25") (pin "2") (pinfunction "2_2") (pintype "passive"))
      (node (ref "C27") (pin "2") (pinfunction "2_2") (pintype "passive"))
      (node (ref "FPC3") (pin "5") (pinfunction "5_5") (pintype "bidirectional"))
      (node (ref "FPC3") (pin "6") (pinfunction "6_6") (pintype "bidirectional"))
      (node (ref "FPC3") (pin "7") (pinfunction "7_7") (pintype "bidirectional"))
      (node (ref "Q1") (pin "3") (pinfunction "D_3") (pintype "bidirectional"))
      (node (ref "R74") (pin "2") (pinfunction "2_2") (pintype "passive"))
    )
    (net (code "31") (name "DONE_1") (class "Default")
      (node (ref "U6") (pin "P$6") (pinfunction "DONE_P$6") (pintype "bidirectional"))
    )
    (net (code "32") (name "DTR") (class "Default")
      (node (ref "R12") (pin "2") (pinfunction "2_2") (pintype "passive"))
      (node (ref "U3") (pin "4") (pinfunction "DTR#_4") (pintype "bidirectional"))
      (node (ref "U4") (pin "4") (pinfunction "E2_4") (pintype "bidirectional"))
    )
    (net (code "33") (name "EC04_A") (class "Default")
      (node (ref "C64") (pin "2") (pinfunction "2_2") (pintype "passive"))
      (node (ref "R62") (pin "2") (pinfunction "2_2") (pintype "passive"))
      (node (ref "U55") (pin "A") (pinfunction "A_A") (pintype "bidirectional"))
      (node (ref "U9") (pin "26") (pinfunction "GPIO20_26") (pintype "bidirectional"))
    )
    (net (code "34") (name "EC04_B") (class "Default")
      (node (ref "C5") (pin "2") (pinfunction "2_2") (pintype "passive"))
      (node (ref "R6") (pin "2") (pinfunction "2_2") (pintype "passive"))
      (node (ref "U55") (pin "B") (pinfunction "B_B") (pintype "bidirectional"))
      (node (ref "U9") (pin "25") (pinfunction "GPIO19_25") (pintype "bidirectional"))
    )
    (net (code "35") (name "ESP32_EN") (class "Default")
      (node (ref "C17") (pin "2") (pinfunction "2_2") (pintype "passive"))
      (node (ref "R14") (pin "2") (pinfunction "2_2") (pintype "passive"))
      (node (ref "SW1") (pin "B") (pinfunction "B_B") (pintype "bidirectional"))
      (node (ref "U4") (pin "6") (pinfunction "C1_6") (pintype "bidirectional"))
      (node (ref "U9") (pin "4") (pinfunction "CHIP_PU_4") (pintype "bidirectional"))
    )
    (net (code "36") (name "ESP_POWER_CTL") (class "Default")
      (node (ref "R27") (pin "2") (pinfunction "2_2") (pintype "passive"))
      (node (ref "U12") (pin "3") (pinfunction "P5.5/SS_3") (pintype "bidirectional"))
    )
    (net (code "37") (name "E_BUTTON") (class "Default")
      (node (ref "C66") (pin "2") (pinfunction "2_2") (pintype "passive"))
      (node (ref "R63") (pin "2") (pinfunction "2_2") (pintype "passive"))
      (node (ref "U55") (pin "D") (pinfunction "D_D") (pintype "bidirectional"))
      (node (ref "U9") (pin "24") (pinfunction "GPIO18_24") (pintype "bidirectional"))
    )
    (net (code "38") (name "I2SOUT_LRCK") (class "Default")
      (node (ref "U11") (pin "2") (pinfunction "LRCLK_2") (pintype "bidirectional"))
      (node (ref "U9") (pin "52") (pinfunction "GPIO46_52") (pintype "bidirectional"))
    )
    (net (code "39") (name "I2SOUT_SCLK") (class "Default")
      (node (ref "U11") (pin "3") (pinfunction "BCLK_3") (pintype "bidirectional"))
      (node (ref "U9") (pin "48") (pinfunction "MTMS_48") (pintype "bidirectional"))
    )
    (net (code "40") (name "I2SOUT_SD") (class "Default")
      (node (ref "U11") (pin "4") (pinfunction "SDATA_4") (pintype "bidirectional"))
      (node (ref "U9") (pin "47") (pinfunction "MTDI_47") (pintype "bidirectional"))
    )
    (net (code "41") (name "IO0_BOOT") (class "Default")
      (node (ref "C21") (pin "2") (pinfunction "2_2") (pintype "passive"))
      (node (ref "R65") (pin "2") (pinfunction "2_2") (pintype "passive"))
      (node (ref "SW2") (pin "B") (pinfunction "B_B") (pintype "bidirectional"))
      (node (ref "U4") (pin "3") (pinfunction "C2_3") (pintype "bidirectional"))
      (node (ref "U9") (pin "5") (pinfunction "GPIO0_5") (pintype "bidirectional"))
    )
    (net (code "42") (name "IO7_LCD_SCK") (class "Default")
      (node (ref "FPC3") (pin "10") (pinfunction "10_10") (pintype "bidirectional"))
      (node (ref "U9") (pin "12") (pinfunction "GPIO7_12") (pintype "bidirectional"))
    )
    (net (code "43") (name "IO8_LCD_MOSI") (class "Default")
      (node (ref "FPC3") (pin "12") (pinfunction "12_12") (pintype "bidirectional"))
      (node (ref "U9") (pin "13") (pinfunction "GPIO8_13") (pintype "bidirectional"))
    )
    (net (code "44") (name "IO9_LCD_CS") (class "Default")
      (node (ref "FPC3") (pin "9") (pinfunction "9_9") (pintype "bidirectional"))
      (node (ref "U9") (pin "14") (pinfunction "GPIO9_14") (pintype "bidirectional"))
    )
    (net (code "45") (name "IO10_LCD_D{slash}C") (class "Default")
      (node (ref "FPC3") (pin "11") (pinfunction "11_11") (pintype "bidirectional"))
      (node (ref "U9") (pin "15") (pinfunction "GPIO10_15") (pintype "bidirectional"))
    )
    (net (code "46") (name "LCD_POWER_DET") (class "Default")
      (node (ref "R7") (pin "2") (pinfunction "2_2") (pintype "passive"))
      (node (ref "U9") (pin "19") (pinfunction "GPIO14_19") (pintype "bidirectional"))
    )
    (net (code "47") (name "LCD_RESET") (class "Default")
      (node (ref "FPC3") (pin "8") (pinfunction "8_8") (pintype "bidirectional"))
      (node (ref "U9") (pin "11") (pinfunction "GPIO6_11") (pintype "bidirectional"))
    )
    (net (code "48") (name "LED") (class "Default")
      (node (ref "R42") (pin "2") (pinfunction "2_2") (pintype "passive"))
      (node (ref "U9") (pin "22") (pinfunction "XTAL_32K_N_22") (pintype "bidirectional"))
    )
    (net (code "49") (name "LEDK") (class "Default")
      (node (ref "FPC3") (pin "15") (pinfunction "15_15") (pintype "bidirectional"))
      (node (ref "Q6") (pin "P$3") (pinfunction "P$3_P$3") (pintype "bidirectional"))
    )
    (net (code "50") (name "MIC_MCLK") (class "Default")
      (node (ref "R43") (pin "2") (pinfunction "2_2") (pintype "passive"))
      (node (ref "U9") (pin "17") (pinfunction "GPIO12_17") (pintype "bidirectional"))
    )
    (net (code "51") (name "MIC_SD2") (class "Default")
      (node (ref "R44") (pin "1") (pinfunction "1_1") (pintype "passive"))
      (node (ref "U9") (pin "16") (pinfunction "GPIO11_16") (pintype "bidirectional"))
    )
    (net (code "52") (name "MIC_VDD_3V3") (class "Default")
      (node (ref "C32") (pin "1") (pinfunction "1_1") (pintype "passive"))
      (node (ref "C33") (pin "1") (pinfunction "1_1") (pintype "passive"))
      (node (ref "FB1") (pin "2") (pinfunction "2_2") (pintype "passive"))
      (node (ref "MIC3") (pin "1") (pinfunction "VDD_1") (pintype "power_in"))
    )
    (net (code "53") (name "Net-(ANT1-PadP$1)") (class "Default")
      (node (ref "ANT1") (pin "P$1") (pinfunction "P$1_P$1") (pintype "bidirectional"))
      (node (ref "L2") (pin "2") (pinfunction "2_2") (pintype "passive"))
    )
    (net (code "54") (name "Net-(C2-Pad2)") (class "Default")
      (node (ref "C2") (pin "2") (pinfunction "2_2") (pintype "passive"))
      (node (ref "D007") (pin "C") (pinfunction "C_C") (pintype "passive"))
      (node (ref "J1") (pin "P$1") (pinfunction "P$1_P$1") (pintype "bidirectional"))
      (node (ref "R1") (pin "2") (pinfunction "2_2") (pintype "passive"))
    )
    (net (code "55") (name "Net-(C4-Pad1)") (class "Default")
      (node (ref "C4") (pin "1") (pinfunction "1_1") (pintype "passive"))
      (node (ref "L1") (pin "2") (pinfunction "2_2") (pintype "passive"))
      (node (ref "L2") (pin "1") (pinfunction "1_1") (pintype "passive"))
    )
    (net (code "56") (name "Net-(D007-PadA)") (class "Default")
      (node (ref "D007") (pin "A") (pinfunction "A_A") (pintype "passive"))
      (node (ref "J1") (pin "P$2") (pinfunction "P$2_P$2") (pintype "bidirectional"))
      (node (ref "Q4") (pin "P$3") (pinfunction "P$3_P$3") (pintype "bidirectional"))
    )
    (net (code "57") (name "Net-(FPC3-Pad13)") (class "Default")
      (node (ref "FPC3") (pin "13") (pinfunction "13_13") (pintype "bidirectional"))
      (node (ref "R70") (pin "2") (pinfunction "2_2") (pintype "passive"))
    )
    (net (code "58") (name "Net-(J3-CC1)") (class "Default")
      (node (ref "J3") (pin "A5") (pinfunction "CC1_A5") (pintype "bidirectional"))
      (node (ref "R20") (pin "1") (pinfunction "1_1") (pintype "passive"))
    )
    (net (code "59") (name "Net-(J3-CC2)") (class "Default")
      (node (ref "J3") (pin "B5") (pinfunction "CC2_B5") (pintype "bidirectional"))
      (node (ref "R19") (pin "2") (pinfunction "2_2") (pintype "passive"))
    )
    (net (code "60") (name "Net-(LED1-Pad+)") (class "Default")
      (node (ref "LED1") (pin "+") (pinfunction "+_+") (pintype "passive"))
      (node (ref "R42") (pin "1") (pinfunction "1_1") (pintype "passive"))
    )
    (net (code "61") (name "Net-(MIC3-CLK)") (class "Default")
      (node (ref "MIC3") (pin "2") (pinfunction "CLK_2") (pintype "input"))
      (node (ref "R43") (pin "1") (pinfunction "1_1") (pintype "passive"))
    )
    (net (code "62") (name "Net-(MIC3-DATA)") (class "Default")
      (node (ref "MIC3") (pin "3") (pinfunction "DATA_3") (pintype "output"))
      (node (ref "R44") (pin "2") (pinfunction "2_2") (pintype "passive"))
    )
    (net (code "63") (name "Net-(MIC3-L{slash}R)") (class "Default")
      (node (ref "MIC3") (pin "5") (pinfunction "L/R_5") (pintype "input"))
      (node (ref "R171") (pin "1") (pinfunction "1_1") (pintype "passive"))
    )
    (net (code "64") (name "Net-(P7-Pad1)") (class "Default")
      (node (ref "P7") (pin "1") (pinfunction "1_1") (pintype "bidirectional"))
      (node (ref "R31") (pin "2") (pinfunction "2_2") (pintype "passive"))
      (node (ref "R33") (pin "2") (pinfunction "2_2") (pintype "passive"))
    )
    (net (code "65") (name "Net-(Q1-G)") (class "Default")
      (node (ref "Q1") (pin "1") (pinfunction "G_1") (pintype "bidirectional"))
      (node (ref "R56") (pin "1") (pinfunction "1_1") (pintype "passive"))
      (node (ref "R57") (pin "1") (pinfunction "1_1") (pintype "passive"))
    )
    (net (code "66") (name "Net-(Q4-PadP$1)") (class "Default")
      (node (ref "Q4") (pin "P$1") (pinfunction "P$1_P$1") (pintype "bidirectional"))
      (node (ref "R2") (pin "2") (pinfunction "2_2") (pintype "passive"))
      (node (ref "R3") (pin "2") (pinfunction "2_2") (pintype "passive"))
    )
    (net (code "67") (name "Net-(Q5-G)") (class "Default")
      (node (ref "Q5") (pin "1") (pinfunction "G_1") (pintype "bidirectional"))
      (node (ref "R37") (pin "1") (pinfunction "1_1") (pintype "passive"))
      (node (ref "R38") (pin "2") (pinfunction "2_2") (pintype "passive"))
    )
    (net (code "68") (name "Net-(Q6-PadP$1)") (class "Default")
      (node (ref "Q6") (pin "P$1") (pinfunction "P$1_P$1") (pintype "bidirectional"))
      (node (ref "R75") (pin "2") (pinfunction "2_2") (pintype "passive"))
      (node (ref "R76") (pin "1") (pinfunction "1_1") (pintype "passive"))
    )
    (net (code "69") (name "Net-(Q7-G)") (class "Default")
      (node (ref "Q7") (pin "1") (pinfunction "G_1") (pintype "passive"))
      (node (ref "R27") (pin "1") (pinfunction "1_1") (pintype "passive"))
      (node (ref "R9") (pin "2") (pinfunction "2_2") (pintype "passive"))
    )
    (net (code "70") (name "Net-(U1-OSCI)") (class "Default")
      (node (ref "C7") (pin "1") (pinfunction "1_1") (pintype "passive"))
      (node (ref "U1") (pin "P$1") (pinfunction "OSCI_P$1") (pintype "bidirectional"))
      (node (ref "Y3") (pin "2") (pinfunction "2_2") (pintype "passive"))
    )
    (net (code "71") (name "Net-(U1-OSCO)") (class "Default")
      (node (ref "C8") (pin "1") (pinfunction "1_1") (pintype "passive"))
      (node (ref "U1") (pin "P$2") (pinfunction "OSCO_P$2") (pintype "bidirectional"))
      (node (ref "Y3") (pin "1") (pinfunction "1_1") (pintype "passive"))
    )
    (net (code "72") (name "Net-(U1-SCL)") (class "Default")
      (node (ref "R16") (pin "2") (pinfunction "2_2") (pintype "passive"))
      (node (ref "U1") (pin "P$6") (pinfunction "SCL_P$6") (pintype "bidirectional"))
    )
    (net (code "73") (name "Net-(U1-SDA)") (class "Default")
      (node (ref "R21") (pin "2") (pinfunction "2_2") (pintype "passive"))
      (node (ref "U1") (pin "P$5") (pinfunction "SDA_P$5") (pintype "bidirectional"))
    )
    (net (code "74") (name "Net-(U3-RXD)") (class "Default")
      (node (ref "R10") (pin "2") (pinfunction "2_2") (pintype "passive"))
      (node (ref "U3") (pin "9") (pinfunction "RXD_9") (pintype "bidirectional"))
    )
    (net (code "75") (name "Net-(U3-TXD)") (class "Default")
      (node (ref "R11") (pin "2") (pinfunction "2_2") (pintype "passive"))
      (node (ref "U3") (pin "8") (pinfunction "TXD_8") (pintype "bidirectional"))
    )
    (net (code "76") (name "Net-(U3-V3)") (class "Default")
      (node (ref "C10") (pin "1") (pinfunction "1_1") (pintype "passive"))
      (node (ref "U3") (pin "10") (pinfunction "V3_10") (pintype "bidirectional"))
    )
    (net (code "77") (name "Net-(U4-B1)") (class "Default")
      (node (ref "R12") (pin "1") (pinfunction "1_1") (pintype "passive"))
      (node (ref "U4") (pin "2") (pinfunction "B1_2") (pintype "input"))
    )
    (net (code "78") (name "Net-(U4-B2)") (class "Default")
      (node (ref "R13") (pin "1") (pinfunction "1_1") (pintype "passive"))
      (node (ref "U4") (pin "5") (pinfunction "B2_5") (pintype "input"))
    )
    (net (code "79") (name "Net-(U6-PROG)") (class "Default")
      (node (ref "R32") (pin "1") (pinfunction "1_1") (pintype "passive"))
      (node (ref "U6") (pin "P$2") (pinfunction "PROG_P$2") (pintype "bidirectional"))
    )
    (net (code "80") (name "Net-(U6-TEMP)") (class "Default")
      (node (ref "R31") (pin "1") (pinfunction "1_1") (pintype "passive"))
      (node (ref "R48") (pin "2") (pinfunction "2_2") (pintype "passive"))
      (node (ref "U6") (pin "P$1") (pinfunction "TEMP_P$1") (pintype "bidirectional"))
    )
    (net (code "81") (name "Net-(U7-CS)") (class "Default")
      (node (ref "R22") (pin "2") (pinfunction "2_2") (pintype "passive"))
      (node (ref "U7") (pin "P$10") (pinfunction "CS_P$10") (pintype "bidirectional"))
    )
    (net (code "82") (name "Net-(U7-SCX)") (class "Default")
      (node (ref "R24") (pin "2") (pinfunction "2_2") (pintype "passive"))
      (node (ref "U7") (pin "P$12") (pinfunction "SCX_P$12") (pintype "bidirectional"))
    )
    (net (code "83") (name "Net-(U7-SDX)") (class "Default")
      (node (ref "R25") (pin "2") (pinfunction "2_2") (pintype "passive"))
      (node (ref "U7") (pin "P$2") (pinfunction "SDX_P$2") (pintype "bidirectional"))
    )
    (net (code "84") (name "Net-(U9-LNA_IN)") (class "Default")
      (node (ref "C3") (pin "1") (pinfunction "1_1") (pintype "passive"))
      (node (ref "L1") (pin "1") (pinfunction "1_1") (pintype "passive"))
      (node (ref "U9") (pin "1") (pinfunction "LNA_IN_1") (pintype "bidirectional"))
    )
    (net (code "85") (name "Net-(U9-VDD3P3_1)") (class "Default")
      (node (ref "C15") (pin "1") (pinfunction "1_1") (pintype "passive"))
      (node (ref "C16") (pin "2") (pinfunction "2_2") (pintype "passive"))
      (node (ref "L4") (pin "1") (pinfunction "1_1") (pintype "passive"))
      (node (ref "U9") (pin "2") (pinfunction "VDD3P3_1_2") (pintype "bidirectional"))
      (node (ref "U9") (pin "3") (pinfunction "VDD3P3_2_3") (pintype "bidirectional"))
    )
    (net (code "86") (name "Net-(U9-XTAL_N)") (class "Default")
      (node (ref "C12") (pin "2") (pinfunction "2_2") (pintype "passive"))
      (node (ref "U9") (pin "53") (pinfunction "XTAL_N_53") (pintype "bidirectional"))
      (node (ref "X1") (pin "3") (pinfunction "X2_3") (pintype "bidirectional"))
    )
    (net (code "87") (name "Net-(U9-XTAL_P)") (class "Default")
      (node (ref "L3") (pin "2") (pinfunction "2_2") (pintype "passive"))
      (node (ref "U9") (pin "54") (pinfunction "XTAL_P_54") (pintype "bidirectional"))
    )
    (net (code "88") (name "Net-(U10-INT)") (class "Default")
      (node (ref "R66") (pin "2") (pinfunction "2_2") (pintype "passive"))
      (node (ref "U10") (pin "20") (pinfunction "INT_20") (pintype "bidirectional"))
    )
    (net (code "89") (name "Net-(U10-IOCAP)") (class "Default")
      (node (ref "C29") (pin "2") (pinfunction "2_2") (pintype "passive"))
      (node (ref "U10") (pin "1") (pinfunction "IOCAP_1") (pintype "bidirectional"))
    )
    (net (code "90") (name "Net-(U10-RESX)") (class "Default")
      (node (ref "R79") (pin "2") (pinfunction "2_2") (pintype "passive"))
      (node (ref "U10") (pin "17") (pinfunction "RESX_17") (pintype "bidirectional"))
    )
    (net (code "91") (name "Net-(U10-SCL)") (class "Default")
      (node (ref "R78") (pin "2") (pinfunction "2_2") (pintype "passive"))
      (node (ref "U10") (pin "18") (pinfunction "SCL_18") (pintype "bidirectional"))
    )
    (net (code "92") (name "Net-(U10-SDA)") (class "Default")
      (node (ref "R77") (pin "2") (pinfunction "2_2") (pintype "passive"))
      (node (ref "U10") (pin "19") (pinfunction "SDA_19") (pintype "bidirectional"))
    )
    (net (code "93") (name "Net-(U10-VCAP)") (class "Default")
      (node (ref "C30") (pin "1") (pinfunction "1_1") (pintype "passive"))
      (node (ref "U10") (pin "15") (pinfunction "VCAP_15") (pintype "bidirectional"))
    )
    (net (code "94") (name "Net-(U11-CTRL)") (class "Default")
      (node (ref "R139") (pin "1") (pinfunction "1_1") (pintype "passive"))
      (node (ref "R143") (pin "2") (pinfunction "2_2") (pintype "passive"))
      (node (ref "U11") (pin "1") (pinfunction "CTRL_1") (pintype "bidirectional"))
    )
    (net (code "95") (name "Net-(U11-VDD)") (class "Default")
      (node (ref "C102") (pin "1") (pinfunction "1_1") (pintype "passive"))
      (node (ref "C103") (pin "1") (pinfunction "1_1") (pintype "passive"))
      (node (ref "C104") (pin "1") (pinfunction "1_1") (pintype "passive"))
      (node (ref "FB17") (pin "1") (pinfunction "1_1") (pintype "passive"))
      (node (ref "U11") (pin "6") (pinfunction "VDD_6") (pintype "bidirectional"))
    )
    (net (code "96") (name "Net-(U11-VON)") (class "Default")
      (node (ref "FB11") (pin "1") (pinfunction "1_1") (pintype "passive"))
      (node (ref "U11") (pin "5") (pinfunction "VON_5") (pintype "bidirectional"))
    )
    (net (code "97") (name "Net-(U11-VOP)") (class "Default")
      (node (ref "FB10") (pin "1") (pinfunction "1_1") (pintype "passive"))
      (node (ref "U11") (pin "8") (pinfunction "VOP_8") (pintype "bidirectional"))
    )
    (net (code "98") (name "Net-(U12-P5.4{slash}MOSI)") (class "Default")
      (node (ref "R7") (pin "1") (pinfunction "1_1") (pintype "passive"))
      (node (ref "U12") (pin "1") (pinfunction "P5.4/MOSI_1") (pintype "bidirectional"))
    )
    (net (code "99") (name "Net-(U13-EN)") (class "Default")
      (node (ref "R4") (pin "2") (pinfunction "2_2") (pintype "passive"))
      (node (ref "U13") (pin "1") (pinfunction "EN_1") (pintype "input"))
    )
    (net (code "100") (name "Net-(U13-FB)") (class "Default")
      (node (ref "C42") (pin "1") (pinfunction "1_1") (pintype "passive"))
      (node (ref "R15") (pin "2") (pinfunction "2_2") (pintype "passive"))
      (node (ref "R17") (pin "1") (pinfunction "1_1") (pintype "passive"))
      (node (ref "U13") (pin "5") (pinfunction "FB_5") (pintype "input"))
    )
    (net (code "101") (name "Net-(U13-SW)") (class "Default")
      (node (ref "L5") (pin "1") (pinfunction "1_1") (pintype "passive"))
      (node (ref "U13") (pin "3") (pinfunction "SW_3") (pintype "bidirectional"))
    )
    (net (code "102") (name "Net-(X1-X1)") (class "Default")
      (node (ref "C11") (pin "2") (pinfunction "2_2") (pintype "passive"))
      (node (ref "L3") (pin "1") (pinfunction "1_1") (pintype "passive"))
      (node (ref "X1") (pin "1") (pinfunction "X1_1") (pintype "bidirectional"))
    )
    (net (code "103") (name "POWER_CTL") (class "Default")
      (node (ref "R4") (pin "1") (pinfunction "1_1") (pintype "passive"))
      (node (ref "U9") (pin "37") (pinfunction "SPICLK_P_37") (pintype "bidirectional"))
    )
    (net (code "104") (name "POWER_KEY") (class "Default")
      (node (ref "C36") (pin "2") (pinfunction "2_2") (pintype "passive"))
      (node (ref "R601") (pin "1") (pinfunction "1_1") (pintype "passive"))
      (node (ref "SW3") (pin "B") (pinfunction "B_B") (pintype "bidirectional"))
      (node (ref "U12") (pin "8") (pinfunction "P3.3/MISO_8") (pintype "bidirectional"))
    )
    (net (code "105") (name "RTS") (class "Default")
      (node (ref "R13") (pin "2") (pinfunction "2_2") (pintype "passive"))
      (node (ref "U3") (pin "6") (pinfunction "RTS#_6") (pintype "bidirectional"))
      (node (ref "U4") (pin "1") (pinfunction "E1_1") (pintype "bidirectional"))
    )
    (net (code "106") (name "RX") (class "Default")
      (node (ref "P9") (pin "P$1") (pinfunction "P$1_P$1") (pintype "bidirectional"))
      (node (ref "U9") (pin "44") (pinfunction "MTCK_44") (pintype "bidirectional"))
    )
    (net (code "107") (name "RXD0_H") (class "Default")
      (node (ref "R11") (pin "1") (pinfunction "1_1") (pintype "passive"))
      (node (ref "U9") (pin "50") (pinfunction "U0RXD_50") (pintype "bidirectional"))
    )
    (net (code "108") (name "SCL") (class "Default")
      (node (ref "P11") (pin "P$1") (pinfunction "P$1_P$1") (pintype "bidirectional"))
      (node (ref "R16") (pin "1") (pinfunction "1_1") (pintype "passive"))
      (node (ref "R24") (pin "1") (pinfunction "1_1") (pintype "passive"))
      (node (ref "R29") (pin "2") (pinfunction "2_2") (pintype "passive"))
      (node (ref "R78") (pin "1") (pinfunction "1_1") (pintype "passive"))
      (node (ref "U9") (pin "8") (pinfunction "GPIO3_8") (pintype "bidirectional"))
    )
    (net (code "109") (name "SDA") (class "Default")
      (node (ref "P14") (pin "P$1") (pinfunction "P$1_P$1") (pintype "bidirectional"))
      (node (ref "R21") (pin "1") (pinfunction "1_1") (pintype "passive"))
      (node (ref "R25") (pin "1") (pinfunction "1_1") (pintype "passive"))
      (node (ref "R26") (pin "2") (pinfunction "2_2") (pintype "passive"))
      (node (ref "R77") (pin "1") (pinfunction "1_1") (pintype "passive"))
      (node (ref "U9") (pin "9") (pinfunction "GPIO4_9") (pintype "bidirectional"))
    )
    (net (code "110") (name "SPICLK") (class "Default")
      (node (ref "U8") (pin "6") (pinfunction "CLK_6") (pintype "bidirectional"))
      (node (ref "U9") (pin "33") (pinfunction "SPICLK_33") (pintype "bidirectional"))
    )
    (net (code "111") (name "SPICS0") (class "Default")
      (node (ref "U8") (pin "1") (pinfunction "/CS_1") (pintype "bidirectional"))
      (node (ref "U9") (pin "32") (pinfunction "SPICS0_32") (pintype "bidirectional"))
    )
    (net (code "112") (name "SPID") (class "Default")
      (node (ref "U8") (pin "5") (pinfunction "DI_(IO0)_5") (pintype "bidirectional"))
      (node (ref "U9") (pin "35") (pinfunction "SPID_35") (pintype "bidirectional"))
    )
    (net (code "113") (name "SPIHD") (class "Default")
      (node (ref "U8") (pin "7") (pinfunction "/HOLD_OR_/RESET_(IO3)_7") (pintype "bidirectional"))
      (node (ref "U9") (pin "30") (pinfunction "SPIHD_30") (pintype "bidirectional"))
    )
    (net (code "114") (name "SPIQ") (class "Default")
      (node (ref "U8") (pin "2") (pinfunction "DO_(IO1)_2") (pintype "bidirectional"))
      (node (ref "U9") (pin "34") (pinfunction "SPIQ_34") (pintype "bidirectional"))
    )
    (net (code "115") (name "SPIWP") (class "Default")
      (node (ref "U8") (pin "3") (pinfunction "/WP_(IO2)_3") (pintype "bidirectional"))
      (node (ref "U9") (pin "31") (pinfunction "SPIWP_31") (pintype "bidirectional"))
    )
    (net (code "116") (name "TE") (class "Default")
      (node (ref "R70") (pin "1") (pinfunction "1_1") (pintype "passive"))
      (node (ref "U9") (pin "27") (pinfunction "GPIO21_27") (pintype "bidirectional"))
    )
    (net (code "117") (name "TOUCH_INT") (class "Default")
      (node (ref "R66") (pin "1") (pinfunction "1_1") (pintype "passive"))
      (node (ref "U9") (pin "7") (pinfunction "GPIO2_7") (pintype "bidirectional"))
    )
    (net (code "118") (name "TOUCH_RST") (class "Default")
      (node (ref "R79") (pin "1") (pinfunction "1_1") (pintype "passive"))
      (node (ref "U9") (pin "10") (pinfunction "GPIO5_10") (pintype "bidirectional"))
    )
    (net (code "119") (name "TX") (class "Default")
      (node (ref "P10") (pin "P$1") (pinfunction "P$1_P$1") (pintype "bidirectional"))
      (node (ref "U9") (pin "43") (pinfunction "GPIO38_43") (pintype "bidirectional"))
    )
    (net (code "120") (name "TXD0_H") (class "Default")
      (node (ref "R10") (pin "1") (pinfunction "1_1") (pintype "passive"))
      (node (ref "U9") (pin "49") (pinfunction "U0TXD_49") (pintype "bidirectional"))
    )
    (net (code "121") (name "USB_D+") (class "Default")
      (node (ref "D1") (pin "2") (pinfunction "2_2") (pintype "bidirectional"))
      (node (ref "R23") (pin "1") (pinfunction "1_1") (pintype "passive"))
      (node (ref "U3") (pin "1") (pinfunction "UD+_1") (pintype "bidirectional"))
    )
    (net (code "122") (name "USB_D-") (class "Default")
      (node (ref "D3") (pin "2") (pinfunction "2_2") (pintype "bidirectional"))
      (node (ref "R18") (pin "1") (pinfunction "1_1") (pintype "passive"))
      (node (ref "U3") (pin "2") (pinfunction "UD-_2") (pintype "bidirectional"))
    )
    (net (code "123") (name "USB_POWER_DET") (class "Default")
      (node (ref "R39") (pin "2") (pinfunction "2_2") (pintype "passive"))
      (node (ref "R40") (pin "2") (pinfunction "2_2") (pintype "passive"))
      (node (ref "U12") (pin "7") (pinfunction "P3.2/SCLK_7") (pintype "bidirectional"))
      (node (ref "U9") (pin "23") (pinfunction "GPIO17_23") (pintype "bidirectional"))
    )
    (net (code "124") (name "VBUS") (class "Default")
      (node (ref "C51") (pin "2") (pinfunction "2_2") (pintype "passive"))
      (node (ref "C9") (pin "1") (pinfunction "1_1") (pintype "passive"))
      (node (ref "D4") (pin "2") (pinfunction "2_2") (pintype "bidirectional"))
      (node (ref "D9") (pin "1") (pinfunction "1_1") (pintype "bidirectional"))
      (node (ref "J3") (pin "A4") (pinfunction "VBUS_A4") (pintype "bidirectional"))
      (node (ref "J3") (pin "A9") (pinfunction "VBUS_A9") (pintype "bidirectional"))
      (node (ref "J3") (pin "B4") (pinfunction "VBUS_B4") (pintype "bidirectional"))
      (node (ref "J3") (pin "B9") (pinfunction "VBUS_B9") (pintype "bidirectional"))
      (node (ref "R37") (pin "2") (pinfunction "2_2") (pintype "passive"))
      (node (ref "R39") (pin "1") (pinfunction "1_1") (pintype "passive"))
      (node (ref "R48") (pin "1") (pinfunction "1_1") (pintype "passive"))
      (node (ref "R5") (pin "1") (pinfunction "1_1") (pintype "passive"))
      (node (ref "U3") (pin "7") (pinfunction "VCC_7") (pintype "bidirectional"))
      (node (ref "U6") (pin "P$4") (pinfunction "VCC_P$4") (pintype "bidirectional"))
      (node (ref "U6") (pin "P$8") (pinfunction "CE_P$8") (pintype "bidirectional"))
    )
    (net (code "125") (name "VCC3V3") (class "Default")
      (node (ref "C18") (pin "2") (pinfunction "2_2") (pintype "passive"))
      (node (ref "C19") (pin "1") (pinfunction "1_1") (pintype "passive"))
      (node (ref "C23") (pin "1") (pinfunction "1_1") (pintype "passive"))
      (node (ref "C31") (pin "1") (pinfunction "1_1") (pintype "passive"))
      (node (ref "L4") (pin "2") (pinfunction "2_2") (pintype "passive"))
      (node (ref "P1") (pin "P$1") (pinfunction "P$1_P$1") (pintype "bidirectional"))
      (node (ref "P15") (pin "P$1") (pinfunction "P$1_P$1") (pintype "bidirectional"))
      (node (ref "Q7") (pin "3") (pinfunction "D_3") (pintype "passive"))
      (node (ref "R14") (pin "1") (pinfunction "1_1") (pintype "passive"))
      (node (ref "R26") (pin "1") (pinfunction "1_1") (pintype "passive"))
      (node (ref "R29") (pin "1") (pinfunction "1_1") (pintype "passive"))
      (node (ref "R6") (pin "1") (pinfunction "1_1") (pintype "passive"))
      (node (ref "R62") (pin "1") (pinfunction "1_1") (pintype "passive"))
      (node (ref "R63") (pin "1") (pinfunction "1_1") (pintype "passive"))
      (node (ref "R65") (pin "1") (pinfunction "1_1") (pintype "passive"))
      (node (ref "U10") (pin "16") (pinfunction "VDDA_16") (pintype "bidirectional"))
      (node (ref "U9") (pin "20") (pinfunction "VDD3P3_RTC_20") (pintype "bidirectional"))
      (node (ref "U9") (pin "46") (pinfunction "VDD3P3_CPU_46") (pintype "bidirectional"))
      (node (ref "U9") (pin "55") (pinfunction "VDDA_1_55") (pintype "bidirectional"))
      (node (ref "U9") (pin "56") (pinfunction "VDDA_2_56") (pintype "bidirectional"))
    )
    (net (code "126") (name "VDD3V3") (class "Default")
      (node (ref "C24") (pin "1") (pinfunction "1_1") (pintype "passive"))
      (node (ref "C28") (pin "1") (pinfunction "1_1") (pintype "passive"))
      (node (ref "C37") (pin "2") (pinfunction "2_2") (pintype "passive"))
      (node (ref "C38") (pin "2") (pinfunction "2_2") (pintype "passive"))
      (node (ref "C39") (pin "2") (pinfunction "2_2") (pintype "passive"))
      (node (ref "P4") (pin "P$1") (pinfunction "P$1_P$1") (pintype "bidirectional"))
      (node (ref "Q7") (pin "2") (pinfunction "S_2") (pintype "passive"))
      (node (ref "R601") (pin "2") (pinfunction "2_2") (pintype "passive"))
      (node (ref "R9") (pin "1") (pinfunction "1_1") (pintype "passive"))
      (node (ref "U1") (pin "P$8") (pinfunction "VDD_P$8") (pintype "bidirectional"))
      (node (ref "U12") (pin "2") (pinfunction "VCC_2") (pintype "bidirectional"))
      (node (ref "U5") (pin "P$5") (pinfunction "OUT_P$5") (pintype "bidirectional"))
    )
    (net (code "127") (name "VDD_SPI") (class "Default")
      (node (ref "C20") (pin "2") (pinfunction "2_2") (pintype "passive"))
      (node (ref "U8") (pin "8") (pinfunction "VCC_8") (pintype "bidirectional"))
      (node (ref "U9") (pin "29") (pinfunction "VDD_SPI_29") (pintype "bidirectional"))
    )
    (net (code "128") (name "VIB_EN") (class "Default")
      (node (ref "R2") (pin "1") (pinfunction "1_1") (pintype "passive"))
      (node (ref "U9") (pin "51") (pinfunction "GPIO45_51") (pintype "bidirectional"))
    )
    (net (code "129") (name "VIN") (class "Default")
      (node (ref "C13") (pin "2") (pinfunction "2_2") (pintype "passive"))
      (node (ref "C34") (pin "2") (pinfunction "2_2") (pintype "passive"))
      (node (ref "C35") (pin "2") (pinfunction "2_2") (pintype "passive"))
      (node (ref "C6") (pin "2") (pinfunction "2_2") (pintype "passive"))
      (node (ref "D9") (pin "2") (pinfunction "2_2") (pintype "bidirectional"))
      (node (ref "Q5") (pin "2") (pinfunction "S_2") (pintype "bidirectional"))
      (node (ref "U13") (pin "4") (pinfunction "VIN_4") (pintype "input"))
      (node (ref "U5") (pin "P$1") (pinfunction "IN_P$1") (pintype "bidirectional"))
      (node (ref "U5") (pin "P$3") (pinfunction "EN_P$3") (pintype "bidirectional"))
    )
    (net (code "130") (name "unconnected-(ANT1-PadP$2)") (class "Default")
      (node (ref "ANT1") (pin "P$2") (pinfunction "P$2_P$2") (pintype "bidirectional"))
    )
    (net (code "131") (name "unconnected-(FPC2-Pad8)") (class "Default")
      (node (ref "FPC2") (pin "8") (pinfunction "8_8") (pintype "bidirectional"))
    )
    (net (code "132") (name "unconnected-(J3-SBU1-PadA8)") (class "Default")
      (node (ref "J3") (pin "A8") (pinfunction "SBU1_A8") (pintype "bidirectional"))
    )
    (net (code "133") (name "unconnected-(J3-SBU2-PadB8)") (class "Default")
      (node (ref "J3") (pin "B8") (pinfunction "SBU2_B8") (pintype "bidirectional"))
    )
    (net (code "134") (name "unconnected-(U1-CLKOUT-PadP$7)") (class "Default")
      (node (ref "U1") (pin "P$7") (pinfunction "CLKOUT_P$7") (pintype "bidirectional"))
    )
    (net (code "135") (name "unconnected-(U1-INT#-PadP$3)") (class "Default")
      (node (ref "U1") (pin "P$3") (pinfunction "INT#_P$3") (pintype "bidirectional"))
    )
    (net (code "136") (name "unconnected-(U3-CTS#-Pad5)") (class "Default")
      (node (ref "U3") (pin "5") (pinfunction "CTS#_5") (pintype "bidirectional"))
    )
    (net (code "137") (name "unconnected-(U5-BP{slash}FB-PadP$4)") (class "Default")
      (node (ref "U5") (pin "P$4") (pinfunction "BP/FB_P$4") (pintype "bidirectional"))
    )
    (net (code "138") (name "unconnected-(U7-INT1-PadP$5)") (class "Default")
      (node (ref "U7") (pin "P$5") (pinfunction "INT1_P$5") (pintype "bidirectional"))
    )
    (net (code "139") (name "unconnected-(U7-INT2-PadP$6)") (class "Default")
      (node (ref "U7") (pin "P$6") (pinfunction "INT2_P$6") (pintype "bidirectional"))
    )
    (net (code "140") (name "unconnected-(U7-NC2-PadP$11)") (class "Default")
      (node (ref "U7") (pin "P$11") (pinfunction "NC2_P$11") (pintype "bidirectional"))
    )
    (net (code "141") (name "unconnected-(U7-SDO-PadP$1)") (class "Default")
      (node (ref "U7") (pin "P$1") (pinfunction "SDO_P$1") (pintype "bidirectional"))
    )
    (net (code "142") (name "unconnected-(U9-GPIO33-Pad38)") (class "Default")
      (node (ref "U9") (pin "38") (pinfunction "GPIO33_38") (pintype "bidirectional"))
    )
    (net (code "143") (name "unconnected-(U9-GPIO34-Pad39)") (class "Default")
      (node (ref "U9") (pin "39") (pinfunction "GPIO34_39") (pintype "bidirectional"))
    )
    (net (code "144") (name "unconnected-(U9-GPIO35-Pad40)") (class "Default")
      (node (ref "U9") (pin "40") (pinfunction "GPIO35_40") (pintype "bidirectional"))
    )
    (net (code "145") (name "unconnected-(U9-GPIO36-Pad41)") (class "Default")
      (node (ref "U9") (pin "41") (pinfunction "GPIO36_41") (pintype "bidirectional"))
    )
    (net (code "146") (name "unconnected-(U9-GPIO37-Pad42)") (class "Default")
      (node (ref "U9") (pin "42") (pinfunction "GPIO37_42") (pintype "bidirectional"))
    )
    (net (code "147") (name "unconnected-(U9-SPICS1-Pad28)") (class "Default")
      (node (ref "U9") (pin "28") (pinfunction "SPICS1_28") (pintype "bidirectional"))
    )
    (net (code "148") (name "unconnected-(U10-S13-Pad14)") (class "Default")
      (node (ref "U10") (pin "14") (pinfunction "S13_14") (pintype "bidirectional"))
    )
  )
)
